# TigardBR.net
KiCad netlist of a schematic drawn in EAGLE
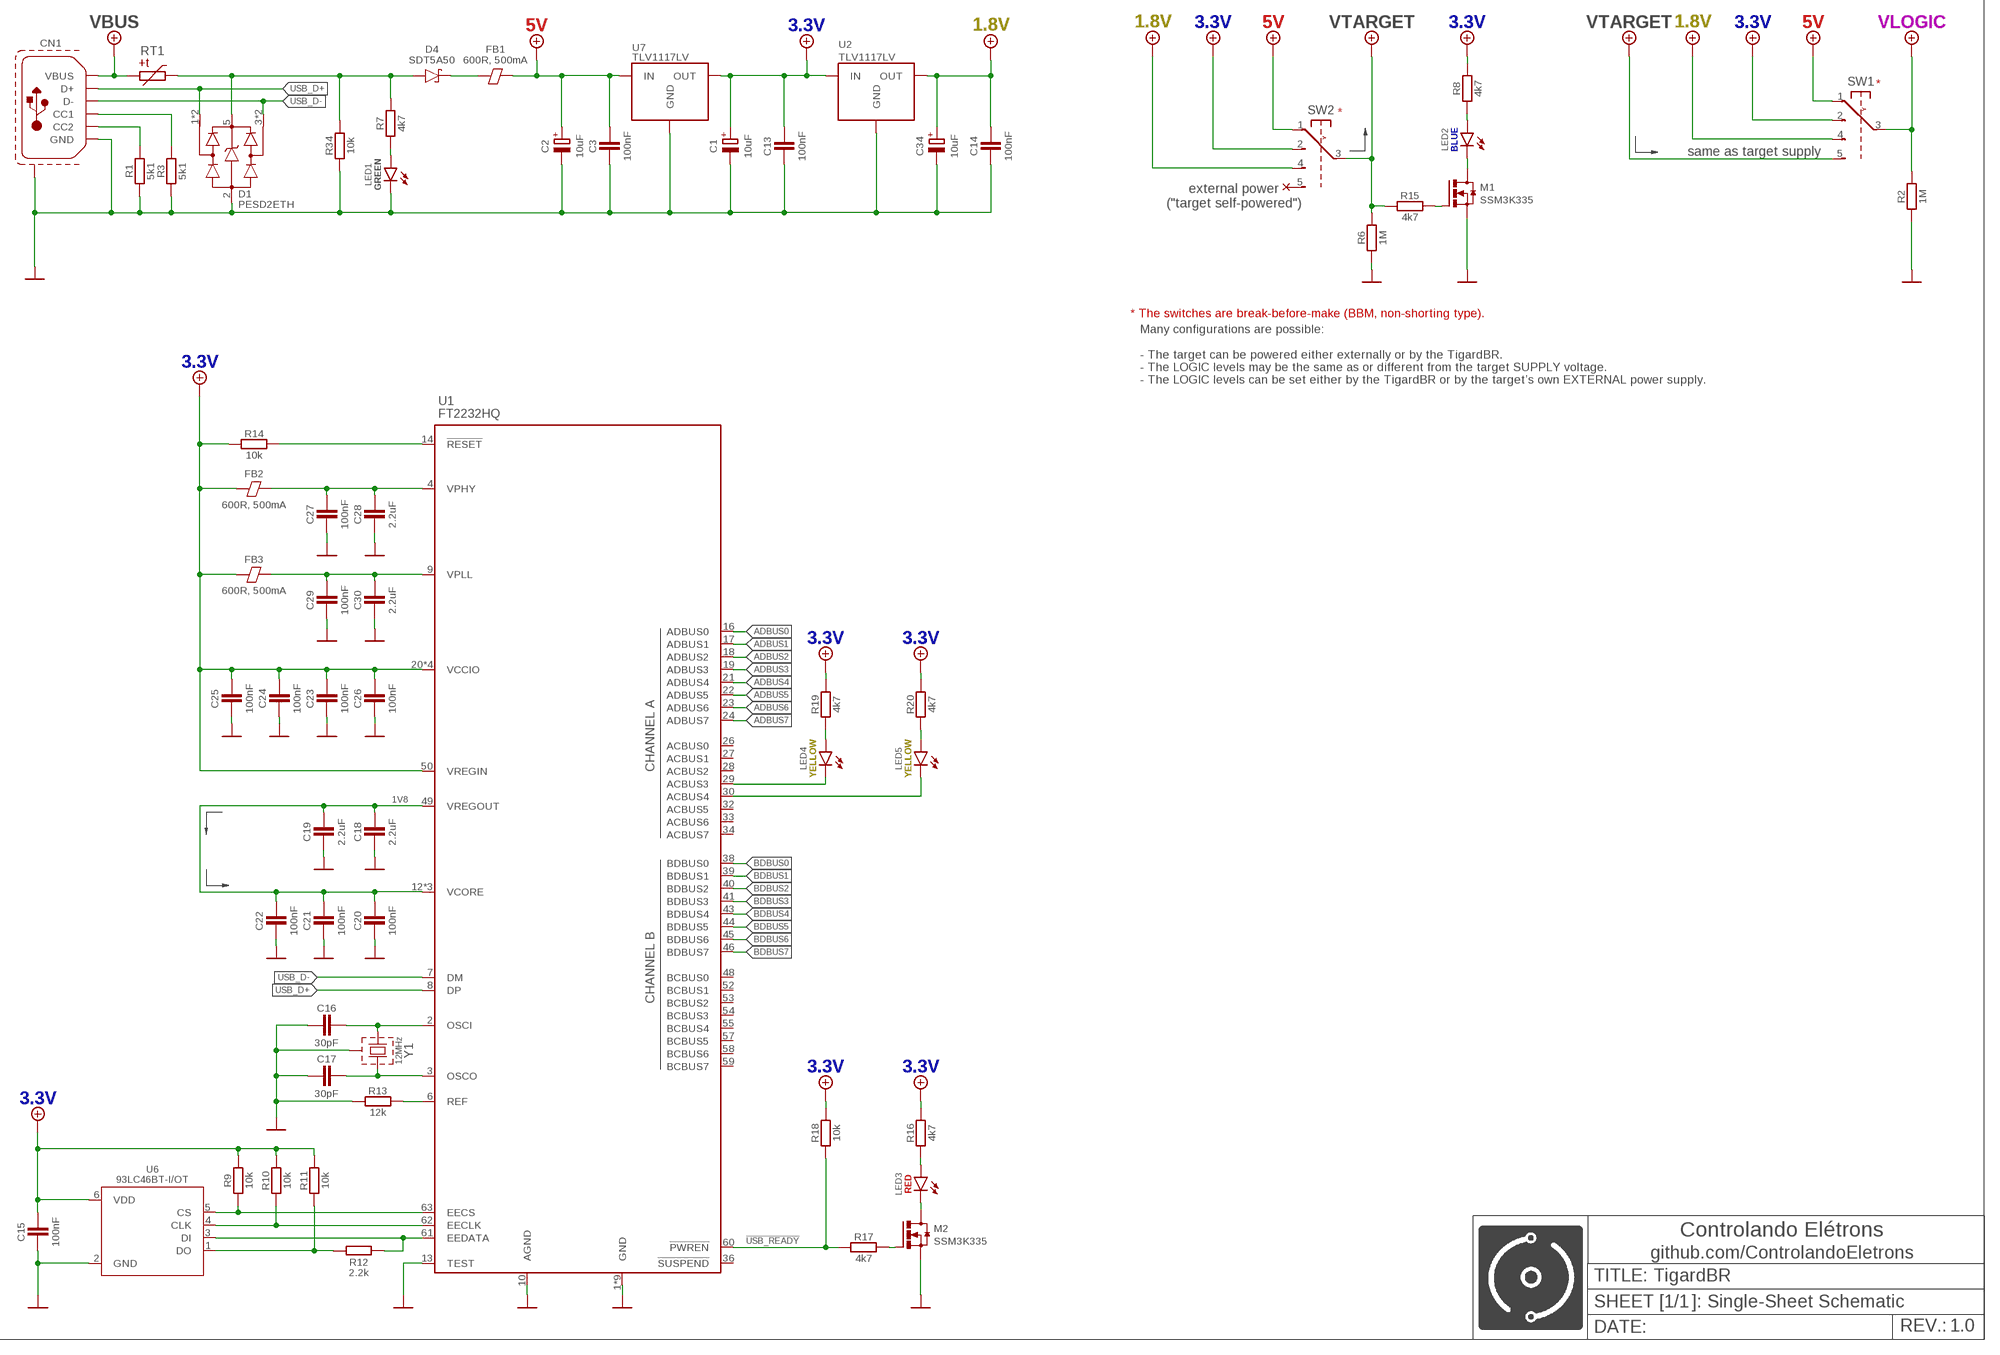
[diagram p0: schematic, sheet 1, part 1 of 3]
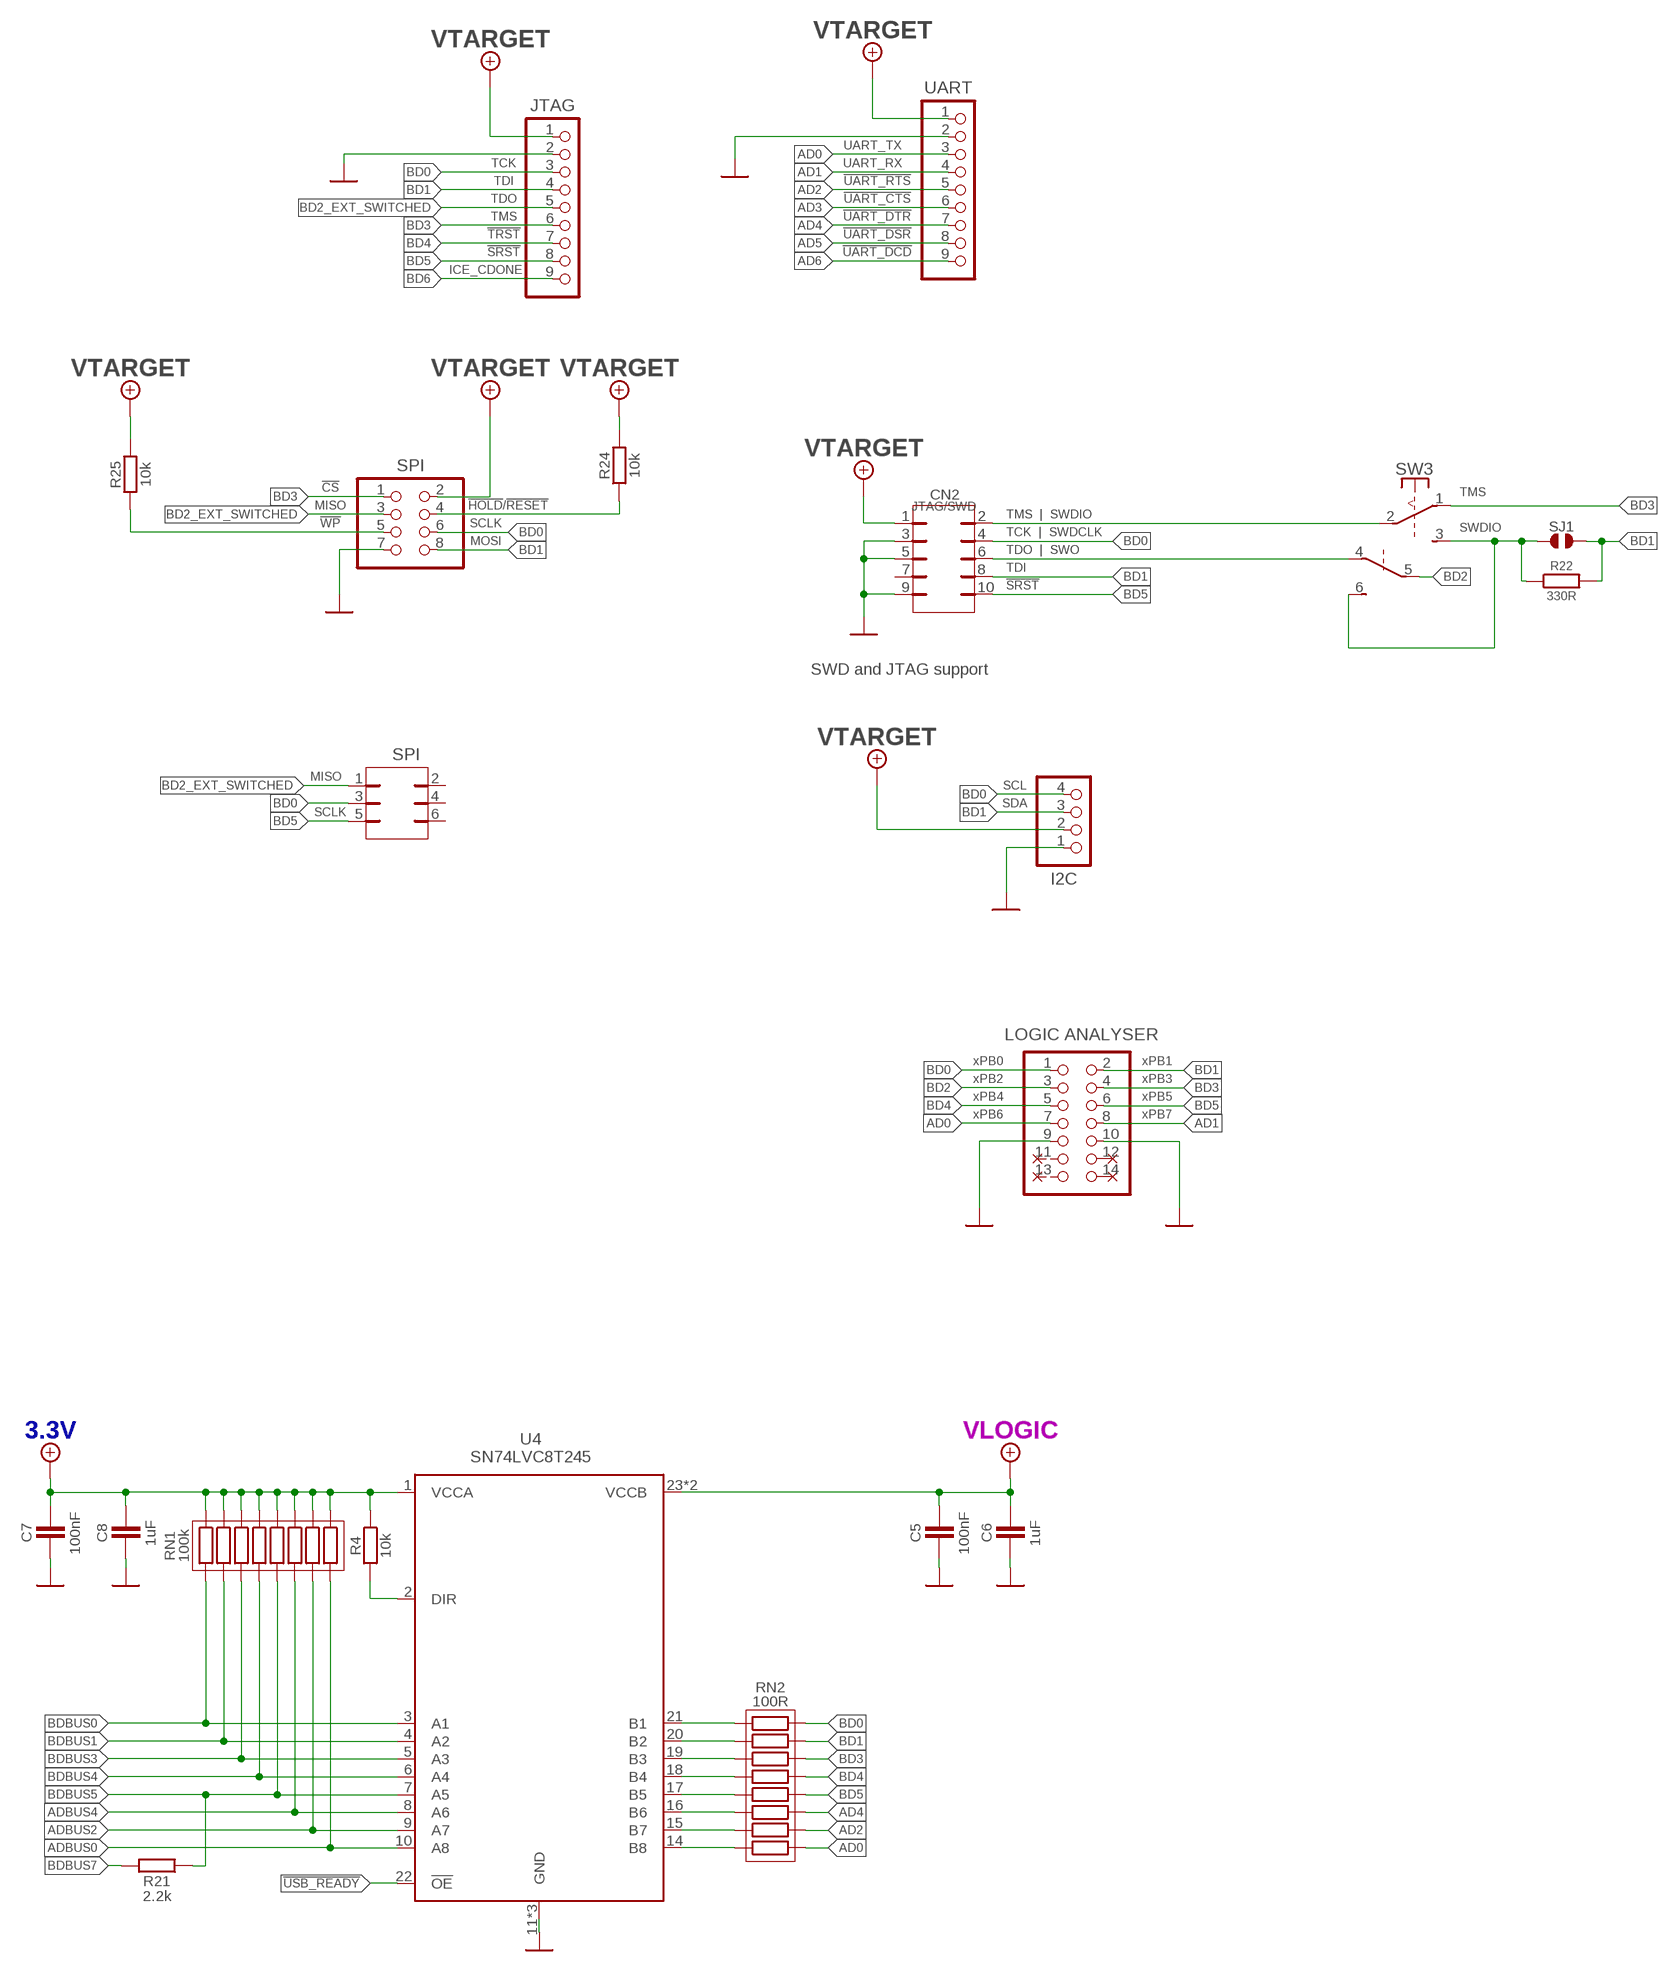
[diagram p1: schematic, sheet 1, part 2 of 3]
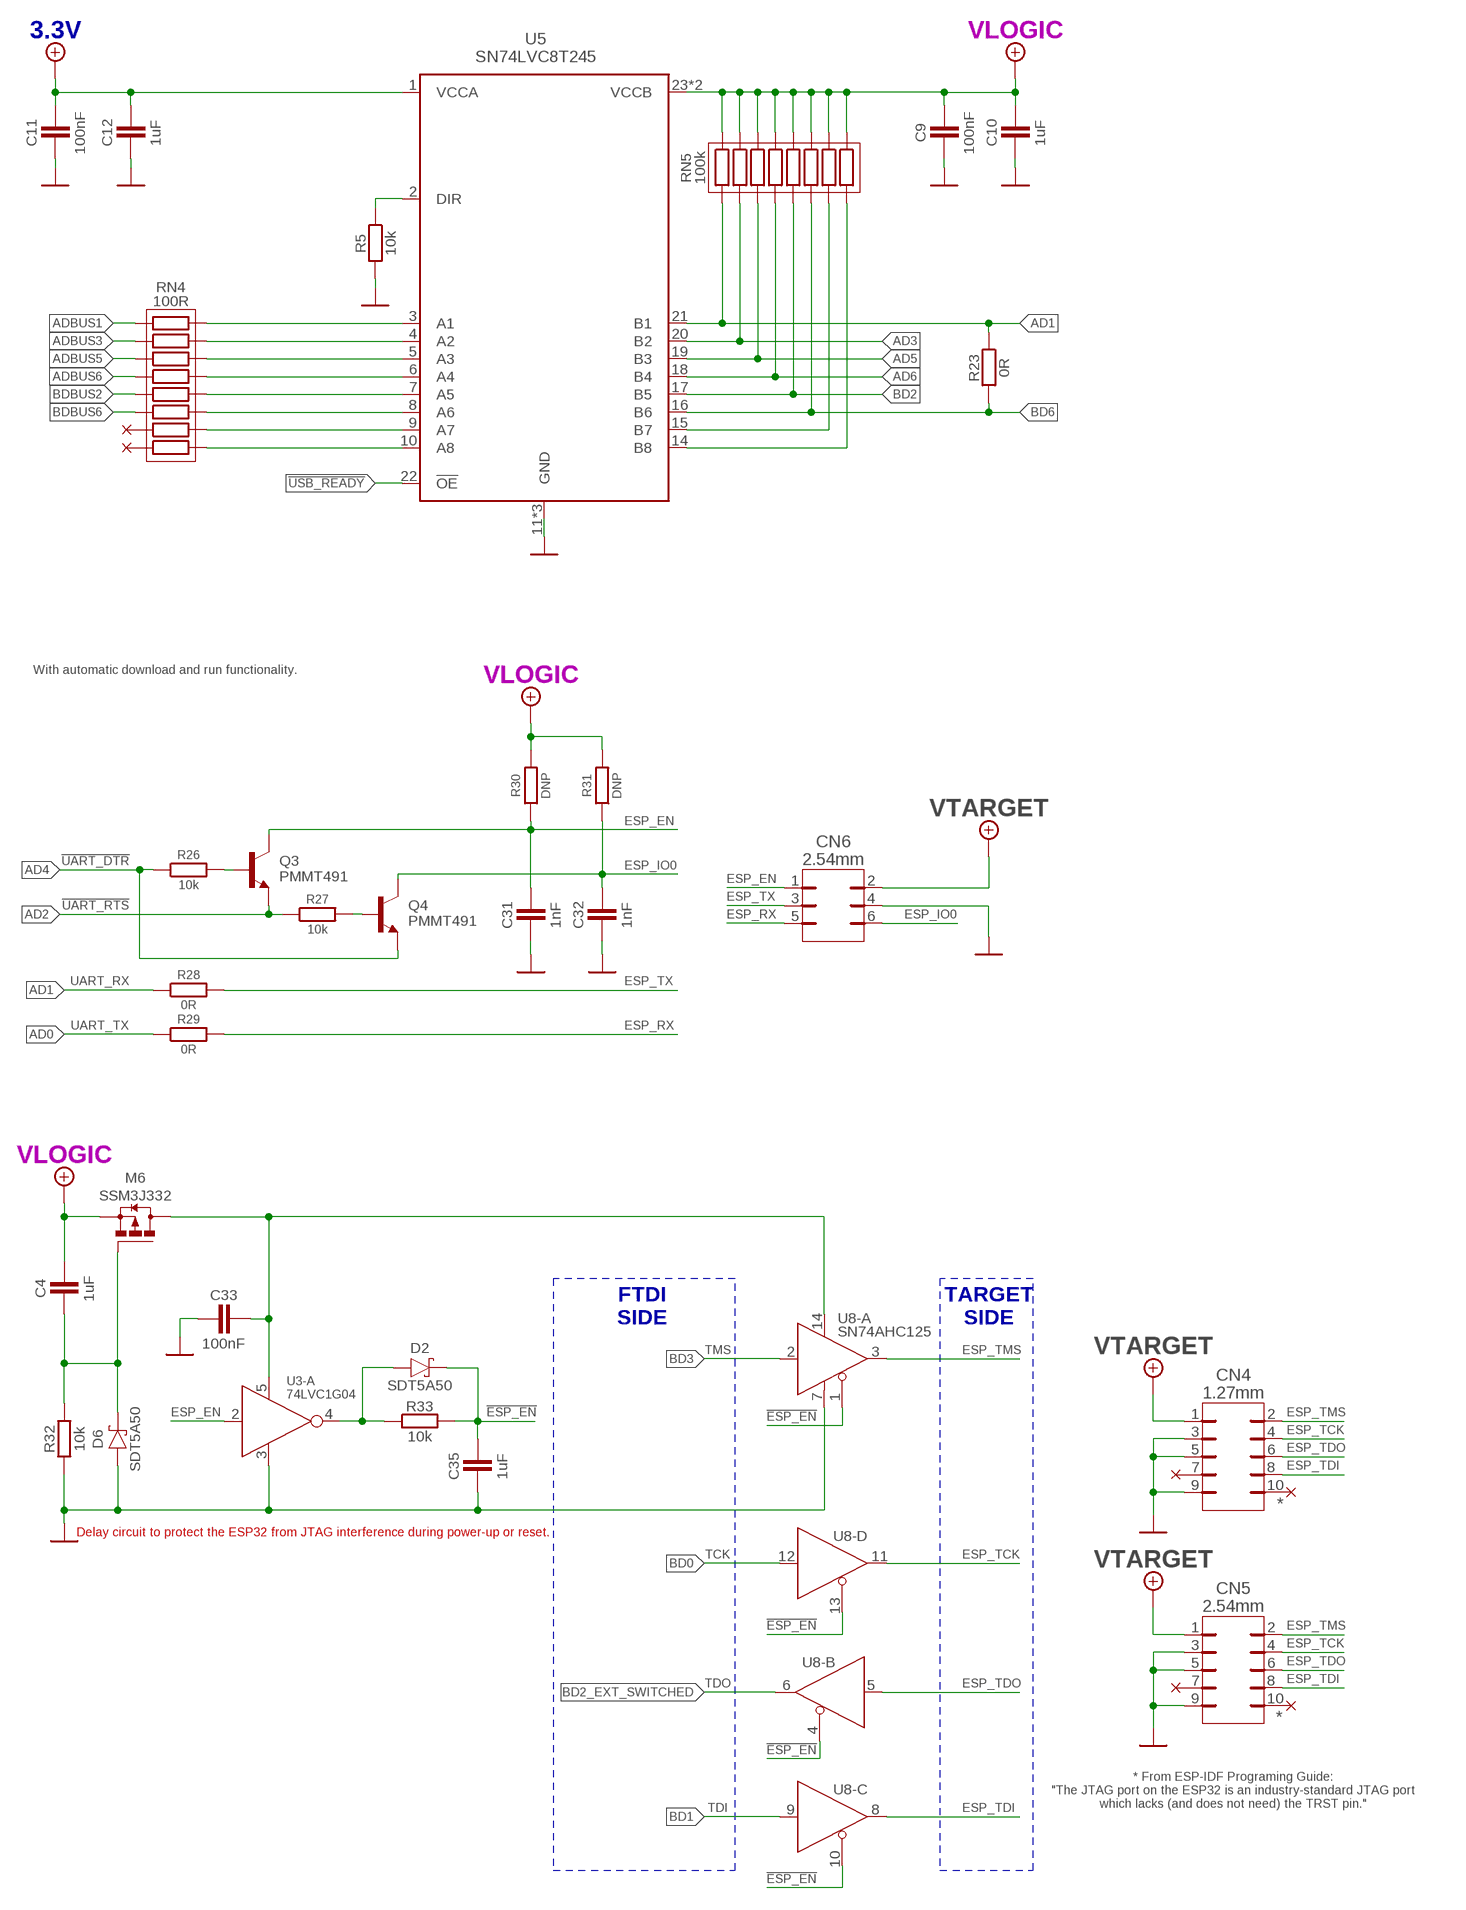
[diagram p2: schematic, sheet 1, part 3 of 3]

(export (version "E")
  (design (tool "Eeschema 10.0.6"))
  (components
    (comp (ref "C1")
      (value "10uF")
      (footprint "eagle-import:C1206_POL")
      (libsource (lib "eagle-import") (part "CP_1206_POL"))
    )
    (comp (ref "C2")
      (value "10uF")
      (footprint "eagle-import:C1206_POL")
      (libsource (lib "eagle-import") (part "CP_1206_POL"))
    )
    (comp (ref "C3")
      (value "100nF")
      (footprint "eagle-import:C0603")
      (libsource (lib "eagle-import") (part "C_0603"))
    )
    (comp (ref "C4")
      (value "1uF")
      (footprint "eagle-import:C0603")
      (libsource (lib "eagle-import") (part "C_0603"))
    )
    (comp (ref "C5")
      (value "100nF")
      (footprint "eagle-import:C0603")
      (libsource (lib "eagle-import") (part "C_0603"))
    )
    (comp (ref "C6")
      (value "1uF")
      (footprint "eagle-import:C0603")
      (libsource (lib "eagle-import") (part "C_0603"))
    )
    (comp (ref "C7")
      (value "100nF")
      (footprint "eagle-import:C0603")
      (libsource (lib "eagle-import") (part "C_0603"))
    )
    (comp (ref "C8")
      (value "1uF")
      (footprint "eagle-import:C0603")
      (libsource (lib "eagle-import") (part "C_0603"))
    )
    (comp (ref "C9")
      (value "100nF")
      (footprint "eagle-import:C0603")
      (libsource (lib "eagle-import") (part "C_0603"))
    )
    (comp (ref "C10")
      (value "1uF")
      (footprint "eagle-import:C0603")
      (libsource (lib "eagle-import") (part "C_0603"))
    )
    (comp (ref "C11")
      (value "100nF")
      (footprint "eagle-import:C0603")
      (libsource (lib "eagle-import") (part "C_0603"))
    )
    (comp (ref "C12")
      (value "1uF")
      (footprint "eagle-import:C0603")
      (libsource (lib "eagle-import") (part "C_0603"))
    )
    (comp (ref "C13")
      (value "100nF")
      (footprint "eagle-import:C0603")
      (libsource (lib "eagle-import") (part "C_0603"))
    )
    (comp (ref "C14")
      (value "100nF")
      (footprint "eagle-import:C0603")
      (libsource (lib "eagle-import") (part "C_0603"))
    )
    (comp (ref "C15")
      (value "100nF")
      (footprint "eagle-import:C0603")
      (libsource (lib "eagle-import") (part "C_0603"))
    )
    (comp (ref "C16")
      (value "30pF")
      (footprint "eagle-import:C0603")
      (libsource (lib "eagle-import") (part "C_0603"))
    )
    (comp (ref "C17")
      (value "30pF")
      (footprint "eagle-import:C0603")
      (libsource (lib "eagle-import") (part "C_0603"))
    )
    (comp (ref "C18")
      (value "2.2uF")
      (footprint "eagle-import:C0603")
      (libsource (lib "eagle-import") (part "C_0603"))
    )
    (comp (ref "C19")
      (value "2.2uF")
      (footprint "eagle-import:C0603")
      (libsource (lib "eagle-import") (part "C_0603"))
    )
    (comp (ref "C20")
      (value "100nF")
      (footprint "eagle-import:C0603")
      (libsource (lib "eagle-import") (part "C_0603"))
    )
    (comp (ref "C21")
      (value "100nF")
      (footprint "eagle-import:C0603")
      (libsource (lib "eagle-import") (part "C_0603"))
    )
    (comp (ref "C22")
      (value "100nF")
      (footprint "eagle-import:C0603")
      (libsource (lib "eagle-import") (part "C_0603"))
    )
    (comp (ref "C23")
      (value "100nF")
      (footprint "eagle-import:C0603")
      (libsource (lib "eagle-import") (part "C_0603"))
    )
    (comp (ref "C24")
      (value "100nF")
      (footprint "eagle-import:C0603")
      (libsource (lib "eagle-import") (part "C_0603"))
    )
    (comp (ref "C25")
      (value "100nF")
      (footprint "eagle-import:C0603")
      (libsource (lib "eagle-import") (part "C_0603"))
    )
    (comp (ref "C26")
      (value "100nF")
      (footprint "eagle-import:C0603")
      (libsource (lib "eagle-import") (part "C_0603"))
    )
    (comp (ref "C27")
      (value "100nF")
      (footprint "eagle-import:C0603")
      (libsource (lib "eagle-import") (part "C_0603"))
    )
    (comp (ref "C28")
      (value "2.2uF")
      (footprint "eagle-import:C0603")
      (libsource (lib "eagle-import") (part "C_0603"))
    )
    (comp (ref "C29")
      (value "100nF")
      (footprint "eagle-import:C0603")
      (libsource (lib "eagle-import") (part "C_0603"))
    )
    (comp (ref "C30")
      (value "2.2uF")
      (footprint "eagle-import:C0603")
      (libsource (lib "eagle-import") (part "C_0603"))
    )
    (comp (ref "C31")
      (value "1nF")
      (footprint "eagle-import:C0603")
      (libsource (lib "eagle-import") (part "C_0603"))
    )
    (comp (ref "C32")
      (value "1nF")
      (footprint "eagle-import:C0603")
      (libsource (lib "eagle-import") (part "C_0603"))
    )
    (comp (ref "C33")
      (value "100nF")
      (footprint "eagle-import:C0603")
      (libsource (lib "eagle-import") (part "C_0603"))
    )
    (comp (ref "C34")
      (value "10uF")
      (footprint "eagle-import:C1206_POL")
      (libsource (lib "eagle-import") (part "CP_1206_POL"))
    )
    (comp (ref "C35")
      (value "1uF")
      (footprint "eagle-import:C0603")
      (libsource (lib "eagle-import") (part "C_0603"))
    )
    (comp (ref "CN1")
      (value "USB-C-16P")
      (footprint "eagle-import:USB-C-16P")
      (libsource (lib "eagle-import") (part "USB-C-16P"))
    )
    (comp (ref "CN2")
      (value "JTAG/SWD")
      (footprint "eagle-import:JTAG-ARM-10P")
      (fields (field (name "PN") "20021121-00010C4LF"))
      (libsource (lib "eagle-import") (part "JTAG"))
    )
    (comp (ref "CN3")
      (value "I2C")
      (footprint "eagle-import:1X04")
      (libsource (lib "eagle-import") (part "PINHD-1X04_2.54"))
    )
    (comp (ref "CN4")
      (value "1.27mm")
      (footprint "eagle-import:JTAG-ARM-10P")
      (fields (field (name "PN") "20021121-00010C4LF"))
      (libsource (lib "eagle-import") (part "JTAG"))
    )
    (comp (ref "CN5")
      (value "2.54mm")
      (footprint "eagle-import:2X05")
      (libsource (lib "eagle-import") (part "PINHD-2X05_2.54"))
    )
    (comp (ref "CN6")
      (value "2.54mm")
      (footprint "eagle-import:2X03")
      (libsource (lib "eagle-import") (part "PINHD-2X03_2.54"))
    )
    (comp (ref "D1")
      (value "TVS-ARRAY-2")
      (footprint "eagle-import:TSOP-6")
      (fields (field (name "FAMILY") "PESD2ETH"))
      (libsource (lib "eagle-import") (part "TVS-ARRAY-2"))
    )
    (comp (ref "D2")
      (value "SDT5A50")
      (footprint "eagle-import:DO-214AC")
      (libsource (lib "eagle-import") (part "SCHOTTKY-SDT5A50SA"))
    )
    (comp (ref "D4")
      (value "SDT5A50")
      (footprint "eagle-import:DO-214AC")
      (libsource (lib "eagle-import") (part "SCHOTTKY-SDT5A50SA"))
    )
    (comp (ref "D6")
      (value "SDT5A50")
      (footprint "eagle-import:DO-214AC")
      (libsource (lib "eagle-import") (part "SCHOTTKY-SDT5A50SA"))
    )
    (comp (ref "FB1")
      (value "600R, 500mA")
      (footprint "eagle-import:L0603")
      (libsource (lib "eagle-import") (part "FB_0603"))
    )
    (comp (ref "FB2")
      (value "600R, 500mA")
      (footprint "eagle-import:L0603")
      (libsource (lib "eagle-import") (part "FB_0603"))
    )
    (comp (ref "FB3")
      (value "600R, 500mA")
      (footprint "eagle-import:L0603")
      (libsource (lib "eagle-import") (part "FB_0603"))
    )
    (comp (ref "JP1")
      (value "JTAG")
      (footprint "eagle-import:1X09")
      (libsource (lib "eagle-import") (part "PINHD-1X09_2.54"))
    )
    (comp (ref "JP2")
      (value "SPI")
      (footprint "eagle-import:2X04")
      (libsource (lib "eagle-import") (part "PINHD-2X04_2.54"))
    )
    (comp (ref "JP3")
      (value "UART")
      (footprint "eagle-import:1X09")
      (libsource (lib "eagle-import") (part "PINHD-1X09_2.54"))
    )
    (comp (ref "JP4")
      (value "LOGIC ANALYSER")
      (footprint "eagle-import:2X07")
      (libsource (lib "eagle-import") (part "PINHD-2X07_2.54"))
    )
    (comp (ref "JP5")
      (value "SPI")
      (footprint "eagle-import:2X03")
      (libsource (lib "eagle-import") (part "PINHD-2X03_2.54"))
    )
    (comp (ref "LED1")
      (value "GREEN")
      (footprint "eagle-import:L0603G")
      (libsource (lib "eagle-import") (part "LED-0603-G"))
    )
    (comp (ref "LED2")
      (value "BLUE")
      (footprint "eagle-import:L0603B")
      (libsource (lib "eagle-import") (part "LED-0603-B"))
    )
    (comp (ref "LED3")
      (value "RED")
      (footprint "eagle-import:L0603R")
      (libsource (lib "eagle-import") (part "LED-0603-R"))
    )
    (comp (ref "LED4")
      (value "YELLOW")
      (footprint "eagle-import:L0603Y")
      (libsource (lib "eagle-import") (part "LED-0603-Y"))
    )
    (comp (ref "LED5")
      (value "YELLOW")
      (footprint "eagle-import:L0603Y")
      (libsource (lib "eagle-import") (part "LED-0603-Y"))
    )
    (comp (ref "M1")
      (value "SSM3K335")
      (footprint "eagle-import:SOT23-3")
      (libsource (lib "eagle-import") (part "MOSFET-N-SSM3K335R"))
    )
    (comp (ref "M2")
      (value "SSM3K335")
      (footprint "eagle-import:SOT23-3")
      (libsource (lib "eagle-import") (part "MOSFET-N-SSM3K335R"))
    )
    (comp (ref "M6")
      (value "SSM3J332")
      (footprint "eagle-import:SOT23-3")
      (libsource (lib "eagle-import") (part "MOSFET-P-SSM3J332R"))
    )
    (comp (ref "Q3")
      (value "PMMT491")
      (footprint "eagle-import:SOT23-3")
      (libsource (lib "eagle-import") (part "BJT-N-PMMT491"))
    )
    (comp (ref "Q4")
      (value "PMMT491")
      (footprint "eagle-import:SOT23-3")
      (libsource (lib "eagle-import") (part "BJT-N-PMMT491"))
    )
    (comp (ref "R1")
      (value "5k1")
      (footprint "eagle-import:R0603")
      (libsource (lib "eagle-import") (part "R_0603"))
    )
    (comp (ref "R2")
      (value "1M")
      (footprint "eagle-import:R0603")
      (libsource (lib "eagle-import") (part "R_0603"))
    )
    (comp (ref "R3")
      (value "5k1")
      (footprint "eagle-import:R0603")
      (libsource (lib "eagle-import") (part "R_0603"))
    )
    (comp (ref "R4")
      (value "10k")
      (footprint "eagle-import:R0603")
      (libsource (lib "eagle-import") (part "R_0603"))
    )
    (comp (ref "R5")
      (value "10k")
      (footprint "eagle-import:R0603")
      (libsource (lib "eagle-import") (part "R_0603"))
    )
    (comp (ref "R6")
      (value "1M")
      (footprint "eagle-import:R0603")
      (libsource (lib "eagle-import") (part "R_0603"))
    )
    (comp (ref "R7")
      (value "4k7")
      (footprint "eagle-import:R0603")
      (libsource (lib "eagle-import") (part "R_0603"))
    )
    (comp (ref "R8")
      (value "4k7")
      (footprint "eagle-import:R0603")
      (libsource (lib "eagle-import") (part "R_0603"))
    )
    (comp (ref "R9")
      (value "10k")
      (footprint "eagle-import:R0603")
      (libsource (lib "eagle-import") (part "R_0603"))
    )
    (comp (ref "R10")
      (value "10k")
      (footprint "eagle-import:R0603")
      (libsource (lib "eagle-import") (part "R_0603"))
    )
    (comp (ref "R11")
      (value "10k")
      (footprint "eagle-import:R0603")
      (libsource (lib "eagle-import") (part "R_0603"))
    )
    (comp (ref "R12")
      (value "2.2k")
      (footprint "eagle-import:R0603")
      (libsource (lib "eagle-import") (part "R_0603"))
    )
    (comp (ref "R13")
      (value "12k")
      (footprint "eagle-import:R0603")
      (libsource (lib "eagle-import") (part "R_0603"))
    )
    (comp (ref "R14")
      (value "10k")
      (footprint "eagle-import:R0603")
      (libsource (lib "eagle-import") (part "R_0603"))
    )
    (comp (ref "R15")
      (value "4k7")
      (footprint "eagle-import:R0603")
      (libsource (lib "eagle-import") (part "R_0603"))
    )
    (comp (ref "R16")
      (value "4k7")
      (footprint "eagle-import:R0603")
      (libsource (lib "eagle-import") (part "R_0603"))
    )
    (comp (ref "R17")
      (value "4k7")
      (footprint "eagle-import:R0603")
      (libsource (lib "eagle-import") (part "R_0603"))
    )
    (comp (ref "R18")
      (value "10k")
      (footprint "eagle-import:R0603")
      (libsource (lib "eagle-import") (part "R_0603"))
    )
    (comp (ref "R19")
      (value "4k7")
      (footprint "eagle-import:R0603")
      (libsource (lib "eagle-import") (part "R_0603"))
    )
    (comp (ref "R20")
      (value "4k7")
      (footprint "eagle-import:R0603")
      (libsource (lib "eagle-import") (part "R_0603"))
    )
    (comp (ref "R21")
      (value "2.2k")
      (footprint "eagle-import:R0603")
      (libsource (lib "eagle-import") (part "R_0603"))
    )
    (comp (ref "R22")
      (value "330R")
      (footprint "eagle-import:R0603")
      (libsource (lib "eagle-import") (part "R_0603"))
    )
    (comp (ref "R23")
      (value "0R")
      (footprint "eagle-import:R0603")
      (libsource (lib "eagle-import") (part "R_0603"))
    )
    (comp (ref "R24")
      (value "10k")
      (footprint "eagle-import:R0603")
      (libsource (lib "eagle-import") (part "R_0603"))
    )
    (comp (ref "R25")
      (value "10k")
      (footprint "eagle-import:R0603")
      (libsource (lib "eagle-import") (part "R_0603"))
    )
    (comp (ref "R26")
      (value "10k")
      (footprint "eagle-import:R0603")
      (libsource (lib "eagle-import") (part "R_0603"))
    )
    (comp (ref "R27")
      (value "10k")
      (footprint "eagle-import:R0603")
      (libsource (lib "eagle-import") (part "R_0603"))
    )
    (comp (ref "R28")
      (value "0R")
      (footprint "eagle-import:R0603")
      (libsource (lib "eagle-import") (part "R_0603"))
    )
    (comp (ref "R29")
      (value "0R")
      (footprint "eagle-import:R0603")
      (libsource (lib "eagle-import") (part "R_0603"))
    )
    (comp (ref "R30")
      (value "DNP")
      (footprint "eagle-import:R0603")
      (libsource (lib "eagle-import") (part "R_0603"))
    )
    (comp (ref "R31")
      (value "DNP")
      (footprint "eagle-import:R0603")
      (libsource (lib "eagle-import") (part "R_0603"))
    )
    (comp (ref "R32")
      (value "10k")
      (footprint "eagle-import:R0603")
      (libsource (lib "eagle-import") (part "R_0603"))
    )
    (comp (ref "R33")
      (value "10k")
      (footprint "eagle-import:R0603")
      (libsource (lib "eagle-import") (part "R_0603"))
    )
    (comp (ref "R34")
      (value "10k")
      (footprint "eagle-import:R0603")
      (libsource (lib "eagle-import") (part "R_0603"))
    )
    (comp (ref "RN1")
      (value "100k")
      (footprint "eagle-import:RN0602")
      (libsource (lib "eagle-import") (part "RN_"))
    )
    (comp (ref "RN2")
      (value "100R")
      (footprint "eagle-import:RN0602")
      (libsource (lib "eagle-import") (part "RN_"))
    )
    (comp (ref "RN4")
      (value "100R")
      (footprint "eagle-import:RN0602")
      (libsource (lib "eagle-import") (part "RN_"))
    )
    (comp (ref "RN5")
      (value "100k")
      (footprint "eagle-import:RN0602")
      (libsource (lib "eagle-import") (part "RN_"))
    )
    (comp (ref "RT1")
      (value "PTC-")
      (footprint "eagle-import:F1812")
      (fields (field (name "TYPE") "+t"))
      (libsource (lib "eagle-import") (part "PTC-"))
    )
    (comp (ref "SJ1")
      (value "2P-NO")
      (footprint "eagle-import:2P-NO-0603")
      (libsource (lib "eagle-import") (part "2P-NO"))
    )
    (comp (ref "SW1")
      (value "DP4T-")
      (footprint "eagle-import:SSSS224100")
      (libsource (lib "eagle-import") (part "DP4T-"))
    )
    (comp (ref "SW2")
      (value "DP4T-")
      (footprint "eagle-import:SSSS224100")
      (libsource (lib "eagle-import") (part "DP4T-"))
    )
    (comp (ref "SW3")
      (value "DP2T-STRAIGHT-SMD")
      (footprint "eagle-import:JS202011SCQN")
      (libsource (lib "eagle-import") (part "DP2T-STRAIGHT-SMD"))
    )
    (comp (ref "U1")
      (value "FT2232HQ")
      (footprint "eagle-import:QFN-64")
      (libsource (lib "eagle-import") (part "FT2232HQ"))
    )
    (comp (ref "U2")
      (value "TLV1117LV")
      (footprint "eagle-import:SOT-223-3")
      (fields (field (name "PN") "TLV1117LV18DCYR"))
      (libsource (lib "eagle-import") (part "1117-3.3V"))
    )
    (comp (ref "U3")
      (value "74LVC1G04")
      (footprint "eagle-import:SOT753-5_(SC-74A)")
      (libsource (lib "eagle-import") (part "SINGLE-INVERTER-74LVC1G04GV"))
    )
    (comp (ref "U4")
      (value "SN74LVC8T245")
      (footprint "eagle-import:TSSOP-24")
      (libsource (lib "eagle-import") (part "SN74LVC8T245"))
    )
    (comp (ref "U5")
      (value "SN74LVC8T245")
      (footprint "eagle-import:TSSOP-24")
      (libsource (lib "eagle-import") (part "SN74LVC8T245"))
    )
    (comp (ref "U6")
      (value "93LC46BT-I/OT")
      (footprint "eagle-import:SOT23-6")
      (libsource (lib "eagle-import") (part "93LC46BT-I/OT"))
    )
    (comp (ref "U7")
      (value "TLV1117LV")
      (footprint "eagle-import:SOT-223-3")
      (libsource (lib "eagle-import") (part "1117-3.3V"))
    )
    (comp (ref "U8")
      (value "SN74AHC125")
      (footprint "eagle-import:SOIC-14")
      (libsource (lib "eagle-import") (part "QUAD-BUFFER-"))
    )
    (comp (ref "Y1")
      (value "12MHz")
      (footprint "eagle-import:3.2MM_2.5MM")
      (libsource (lib "eagle-import") (part "OSC-CHASSI-"))
    )
  )
  (nets
    (net (code "1") (name "/1V8") (class "Default")
      (node (ref "C18") (pin "1") (pinfunction "1_1") (pintype "passive"))
      (node (ref "C19") (pin "1") (pinfunction "1_1") (pintype "passive"))
      (node (ref "C20") (pin "1") (pinfunction "1_1") (pintype "passive"))
      (node (ref "C21") (pin "1") (pinfunction "1_1") (pintype "passive"))
      (node (ref "C22") (pin "1") (pinfunction "1_1") (pintype "passive"))
      (node (ref "U1") (pin "12") (pinfunction "VCORE_12") (pintype "bidirectional"))
      (node (ref "U1") (pin "37") (pinfunction "VCORE_37") (pintype "bidirectional"))
      (node (ref "U1") (pin "49") (pinfunction "VREGOUT_49") (pintype "bidirectional"))
      (node (ref "U1") (pin "64") (pinfunction "VCORE_64") (pintype "bidirectional"))
    )
    (net (code "2") (name "/ESP_EN") (class "Default")
      (node (ref "C31") (pin "1") (pinfunction "1_1") (pintype "passive"))
      (node (ref "CN6") (pin "1") (pinfunction "1_1") (pintype "passive"))
      (node (ref "Q3") (pin "3") (pinfunction "C_3") (pintype "passive"))
      (node (ref "R30") (pin "1") (pinfunction "1_1") (pintype "passive"))
      (node (ref "U3") (pin "2") (pinfunction "A_2") (pintype "bidirectional"))
    )
    (net (code "3") (name "/ESP_IO0") (class "Default")
      (node (ref "C32") (pin "1") (pinfunction "1_1") (pintype "passive"))
      (node (ref "CN6") (pin "6") (pinfunction "6_6") (pintype "passive"))
      (node (ref "Q4") (pin "3") (pinfunction "C_3") (pintype "passive"))
      (node (ref "R31") (pin "1") (pinfunction "1_1") (pintype "passive"))
    )
    (net (code "4") (name "/ESP_RX") (class "Default")
      (node (ref "CN6") (pin "5") (pinfunction "5_5") (pintype "passive"))
      (node (ref "R29") (pin "2") (pinfunction "2_2") (pintype "passive"))
    )
    (net (code "5") (name "/ESP_TCK") (class "Default")
      (node (ref "CN4") (pin "4") (pinfunction "TCK_4") (pintype "bidirectional"))
      (node (ref "CN5") (pin "4") (pinfunction "4_4") (pintype "passive"))
      (node (ref "U8") (pin "11") (pinfunction "Y_11") (pintype "bidirectional"))
    )
    (net (code "6") (name "/ESP_TDI") (class "Default")
      (node (ref "CN4") (pin "8") (pinfunction "TDI_8") (pintype "bidirectional"))
      (node (ref "CN5") (pin "8") (pinfunction "8_8") (pintype "passive"))
      (node (ref "U8") (pin "8") (pinfunction "Y_8") (pintype "bidirectional"))
    )
    (net (code "7") (name "/ESP_TDO") (class "Default")
      (node (ref "CN4") (pin "6") (pinfunction "TDO_6") (pintype "bidirectional"))
      (node (ref "CN5") (pin "6") (pinfunction "6_6") (pintype "passive"))
      (node (ref "U8") (pin "5") (pinfunction "A_5") (pintype "bidirectional"))
    )
    (net (code "8") (name "/ESP_TMS") (class "Default")
      (node (ref "CN4") (pin "2") (pinfunction "TMS_2") (pintype "bidirectional"))
      (node (ref "CN5") (pin "2") (pinfunction "2_2") (pintype "passive"))
      (node (ref "U8") (pin "3") (pinfunction "Y_3") (pintype "bidirectional"))
    )
    (net (code "9") (name "/ESP_TX") (class "Default")
      (node (ref "CN6") (pin "3") (pinfunction "3_3") (pintype "passive"))
      (node (ref "R28") (pin "2") (pinfunction "2_2") (pintype "passive"))
    )
    (net (code "10") (name "/~{ESP_EN}") (class "Default")
      (node (ref "C35") (pin "1") (pinfunction "1_1") (pintype "passive"))
      (node (ref "D2") (pin "1") (pinfunction "K_1") (pintype "passive"))
      (node (ref "R33") (pin "2") (pinfunction "2_2") (pintype "passive"))
      (node (ref "U8") (pin "1") (pinfunction "~{OE}_1") (pintype "bidirectional"))
      (node (ref "U8") (pin "10") (pinfunction "~{OE}_10") (pintype "bidirectional"))
      (node (ref "U8") (pin "13") (pinfunction "~{OE}_13") (pintype "bidirectional"))
      (node (ref "U8") (pin "4") (pinfunction "~{OE}_4") (pintype "bidirectional"))
    )
    (net (code "11") (name "/~{USB_READY}") (class "Default")
      (node (ref "R17") (pin "1") (pinfunction "1_1") (pintype "passive"))
      (node (ref "R18") (pin "2") (pinfunction "2_2") (pintype "passive"))
      (node (ref "U1") (pin "60") (pinfunction "~{PWREN}_60") (pintype "bidirectional"))
      (node (ref "U4") (pin "22") (pinfunction "~{OE}_22") (pintype "bidirectional"))
      (node (ref "U5") (pin "22") (pinfunction "~{OE}_22") (pintype "bidirectional"))
    )
    (net (code "12") (name "0V") (class "Default")
      (node (ref "C1") (pin "2") (pinfunction "-_2") (pintype "passive"))
      (node (ref "C10") (pin "2") (pinfunction "2_2") (pintype "passive"))
      (node (ref "C11") (pin "2") (pinfunction "2_2") (pintype "passive"))
      (node (ref "C12") (pin "2") (pinfunction "2_2") (pintype "passive"))
      (node (ref "C13") (pin "2") (pinfunction "2_2") (pintype "passive"))
      (node (ref "C14") (pin "2") (pinfunction "2_2") (pintype "passive"))
      (node (ref "C15") (pin "2") (pinfunction "2_2") (pintype "passive"))
      (node (ref "C16") (pin "2") (pinfunction "2_2") (pintype "passive"))
      (node (ref "C17") (pin "2") (pinfunction "2_2") (pintype "passive"))
      (node (ref "C18") (pin "2") (pinfunction "2_2") (pintype "passive"))
      (node (ref "C19") (pin "2") (pinfunction "2_2") (pintype "passive"))
      (node (ref "C2") (pin "2") (pinfunction "-_2") (pintype "passive"))
      (node (ref "C20") (pin "2") (pinfunction "2_2") (pintype "passive"))
      (node (ref "C21") (pin "2") (pinfunction "2_2") (pintype "passive"))
      (node (ref "C22") (pin "2") (pinfunction "2_2") (pintype "passive"))
      (node (ref "C23") (pin "2") (pinfunction "2_2") (pintype "passive"))
      (node (ref "C24") (pin "2") (pinfunction "2_2") (pintype "passive"))
      (node (ref "C25") (pin "2") (pinfunction "2_2") (pintype "passive"))
      (node (ref "C26") (pin "2") (pinfunction "2_2") (pintype "passive"))
      (node (ref "C27") (pin "2") (pinfunction "2_2") (pintype "passive"))
      (node (ref "C28") (pin "2") (pinfunction "2_2") (pintype "passive"))
      (node (ref "C29") (pin "2") (pinfunction "2_2") (pintype "passive"))
      (node (ref "C3") (pin "2") (pinfunction "2_2") (pintype "passive"))
      (node (ref "C30") (pin "2") (pinfunction "2_2") (pintype "passive"))
      (node (ref "C31") (pin "2") (pinfunction "2_2") (pintype "passive"))
      (node (ref "C32") (pin "2") (pinfunction "2_2") (pintype "passive"))
      (node (ref "C33") (pin "2") (pinfunction "2_2") (pintype "passive"))
      (node (ref "C34") (pin "2") (pinfunction "-_2") (pintype "passive"))
      (node (ref "C35") (pin "2") (pinfunction "2_2") (pintype "passive"))
      (node (ref "C5") (pin "2") (pinfunction "2_2") (pintype "passive"))
      (node (ref "C6") (pin "2") (pinfunction "2_2") (pintype "passive"))
      (node (ref "C7") (pin "2") (pinfunction "2_2") (pintype "passive"))
      (node (ref "C8") (pin "2") (pinfunction "2_2") (pintype "passive"))
      (node (ref "C9") (pin "2") (pinfunction "2_2") (pintype "passive"))
      (node (ref "CN1") (pin "A1_B12") (pinfunction "GND_A1_B12") (pintype "bidirectional"))
      (node (ref "CN1") (pin "B1_A12") (pinfunction "GND_B1_A12") (pintype "bidirectional"))
      (node (ref "CN1") (pin "S1") (pinfunction "CHASSI_S1") (pintype "passive"))
      (node (ref "CN1") (pin "S2") (pinfunction "CHASSI_S2") (pintype "passive"))
      (node (ref "CN1") (pin "S3") (pinfunction "CHASSI_S3") (pintype "passive"))
      (node (ref "CN1") (pin "S4") (pinfunction "CHASSI_S4") (pintype "passive"))
      (node (ref "CN2") (pin "3") (pinfunction "GND_3") (pintype "bidirectional"))
      (node (ref "CN2") (pin "5") (pinfunction "GND2_5") (pintype "bidirectional"))
      (node (ref "CN2") (pin "9") (pinfunction "GND3_9") (pintype "bidirectional"))
      (node (ref "CN3") (pin "1") (pinfunction "1_1") (pintype "passive"))
      (node (ref "CN4") (pin "3") (pinfunction "GND_3") (pintype "bidirectional"))
      (node (ref "CN4") (pin "5") (pinfunction "GND2_5") (pintype "bidirectional"))
      (node (ref "CN4") (pin "9") (pinfunction "GND3_9") (pintype "bidirectional"))
      (node (ref "CN5") (pin "3") (pinfunction "3_3") (pintype "passive"))
      (node (ref "CN5") (pin "5") (pinfunction "5_5") (pintype "passive"))
      (node (ref "CN5") (pin "9") (pinfunction "9_9") (pintype "passive"))
      (node (ref "CN6") (pin "4") (pinfunction "4_4") (pintype "passive"))
      (node (ref "D1") (pin "2") (pinfunction "GND_2") (pintype "power_in"))
      (node (ref "D6") (pin "2") (pinfunction "A_2") (pintype "passive"))
      (node (ref "JP1") (pin "2") (pinfunction "2_2") (pintype "passive"))
      (node (ref "JP2") (pin "7") (pinfunction "7_7") (pintype "passive"))
      (node (ref "JP3") (pin "2") (pinfunction "2_2") (pintype "passive"))
      (node (ref "JP4") (pin "10") (pinfunction "10_10") (pintype "passive"))
      (node (ref "JP4") (pin "9") (pinfunction "9_9") (pintype "passive"))
      (node (ref "LED1") (pin "K") (pinfunction "K_K") (pintype "passive"))
      (node (ref "M1") (pin "2") (pinfunction "S_2") (pintype "passive"))
      (node (ref "M2") (pin "2") (pinfunction "S_2") (pintype "passive"))
      (node (ref "R1") (pin "1") (pinfunction "1_1") (pintype "passive"))
      (node (ref "R13") (pin "2") (pinfunction "2_2") (pintype "passive"))
      (node (ref "R2") (pin "1") (pinfunction "1_1") (pintype "passive"))
      (node (ref "R3") (pin "1") (pinfunction "1_1") (pintype "passive"))
      (node (ref "R32") (pin "1") (pinfunction "1_1") (pintype "passive"))
      (node (ref "R34") (pin "1") (pinfunction "1_1") (pintype "passive"))
      (node (ref "R5") (pin "2") (pinfunction "2_2") (pintype "passive"))
      (node (ref "R6") (pin "1") (pinfunction "1_1") (pintype "passive"))
      (node (ref "U1") (pin "1") (pinfunction "GND_1") (pintype "bidirectional"))
      (node (ref "U1") (pin "10") (pinfunction "AGND_10") (pintype "bidirectional"))
      (node (ref "U1") (pin "11") (pinfunction "GND_11") (pintype "bidirectional"))
      (node (ref "U1") (pin "13") (pinfunction "TEST_13") (pintype "bidirectional"))
      (node (ref "U1") (pin "15") (pinfunction "GND_15") (pintype "bidirectional"))
      (node (ref "U1") (pin "25") (pinfunction "GND_25") (pintype "bidirectional"))
      (node (ref "U1") (pin "35") (pinfunction "GND_35") (pintype "bidirectional"))
      (node (ref "U1") (pin "47") (pinfunction "GND_47") (pintype "bidirectional"))
      (node (ref "U1") (pin "5") (pinfunction "GND_5") (pintype "bidirectional"))
      (node (ref "U1") (pin "51") (pinfunction "GND_51") (pintype "bidirectional"))
      (node (ref "U1") (pin "TP") (pinfunction "GND_TP") (pintype "bidirectional"))
      (node (ref "U2") (pin "1") (pinfunction "GND_1") (pintype "bidirectional"))
      (node (ref "U3") (pin "3") (pinfunction "VSS_3") (pintype "power_in"))
      (node (ref "U4") (pin "11") (pinfunction "GND_11") (pintype "bidirectional"))
      (node (ref "U4") (pin "12") (pinfunction "GND_12") (pintype "bidirectional"))
      (node (ref "U4") (pin "13") (pinfunction "GND_13") (pintype "bidirectional"))
      (node (ref "U5") (pin "11") (pinfunction "GND_11") (pintype "bidirectional"))
      (node (ref "U5") (pin "12") (pinfunction "GND_12") (pintype "bidirectional"))
      (node (ref "U5") (pin "13") (pinfunction "GND_13") (pintype "bidirectional"))
      (node (ref "U6") (pin "2") (pinfunction "GND_2") (pintype "bidirectional"))
      (node (ref "U7") (pin "1") (pinfunction "GND_1") (pintype "bidirectional"))
      (node (ref "U8") (pin "7") (pinfunction "VSS_7") (pintype "bidirectional"))
      (node (ref "Y1") (pin "2") (pinfunction "CH_2") (pintype "bidirectional"))
      (node (ref "Y1") (pin "4") (pinfunction "CH_4") (pintype "bidirectional"))
    )
    (net (code "13") (name "1.8V") (class "Default")
      (node (ref "C14") (pin "1") (pinfunction "1_1") (pintype "passive"))
      (node (ref "C34") (pin "1") (pinfunction "+_1") (pintype "passive"))
      (node (ref "SW1") (pin "4") (pinfunction "NO2_4") (pintype "passive"))
      (node (ref "SW2") (pin "4") (pinfunction "NO2_4") (pintype "passive"))
      (node (ref "U2") (pin "2") (pinfunction "OUT_2") (pintype "bidirectional"))
      (node (ref "U2") (pin "4") (pinfunction "OUT_4") (pintype "bidirectional"))
    )
    (net (code "14") (name "3.3V") (class "Default")
      (node (ref "C1") (pin "1") (pinfunction "+_1") (pintype "passive"))
      (node (ref "C11") (pin "1") (pinfunction "1_1") (pintype "passive"))
      (node (ref "C12") (pin "1") (pinfunction "1_1") (pintype "passive"))
      (node (ref "C13") (pin "1") (pinfunction "1_1") (pintype "passive"))
      (node (ref "C15") (pin "1") (pinfunction "1_1") (pintype "passive"))
      (node (ref "C23") (pin "1") (pinfunction "1_1") (pintype "passive"))
      (node (ref "C24") (pin "1") (pinfunction "1_1") (pintype "passive"))
      (node (ref "C25") (pin "1") (pinfunction "1_1") (pintype "passive"))
      (node (ref "C26") (pin "1") (pinfunction "1_1") (pintype "passive"))
      (node (ref "C7") (pin "1") (pinfunction "1_1") (pintype "passive"))
      (node (ref "C8") (pin "1") (pinfunction "1_1") (pintype "passive"))
      (node (ref "FB2") (pin "1") (pinfunction "1_1") (pintype "passive"))
      (node (ref "FB3") (pin "1") (pinfunction "1_1") (pintype "passive"))
      (node (ref "R10") (pin "1") (pinfunction "1_1") (pintype "passive"))
      (node (ref "R11") (pin "1") (pinfunction "1_1") (pintype "passive"))
      (node (ref "R14") (pin "2") (pinfunction "2_2") (pintype "passive"))
      (node (ref "R16") (pin "2") (pinfunction "2_2") (pintype "passive"))
      (node (ref "R18") (pin "1") (pinfunction "1_1") (pintype "passive"))
      (node (ref "R19") (pin "2") (pinfunction "2_2") (pintype "passive"))
      (node (ref "R20") (pin "2") (pinfunction "2_2") (pintype "passive"))
      (node (ref "R4") (pin "1") (pinfunction "1_1") (pintype "passive"))
      (node (ref "R8") (pin "2") (pinfunction "2_2") (pintype "passive"))
      (node (ref "R9") (pin "1") (pinfunction "1_1") (pintype "passive"))
      (node (ref "RN1") (pin "1") (pinfunction "1_1") (pintype "passive"))
      (node (ref "RN1") (pin "2") (pinfunction "2_2") (pintype "passive"))
      (node (ref "RN1") (pin "3") (pinfunction "3_3") (pintype "passive"))
      (node (ref "RN1") (pin "4") (pinfunction "4_4") (pintype "passive"))
      (node (ref "RN1") (pin "5") (pinfunction "5_5") (pintype "passive"))
      (node (ref "RN1") (pin "6") (pinfunction "6_6") (pintype "passive"))
      (node (ref "RN1") (pin "7") (pinfunction "7_7") (pintype "passive"))
      (node (ref "RN1") (pin "8") (pinfunction "8_8") (pintype "passive"))
      (node (ref "SW1") (pin "2") (pinfunction "NO1_2") (pintype "passive"))
      (node (ref "SW2") (pin "2") (pinfunction "NO1_2") (pintype "passive"))
      (node (ref "U1") (pin "20") (pinfunction "VCCIO_20") (pintype "bidirectional"))
      (node (ref "U1") (pin "31") (pinfunction "VCCIO_31") (pintype "bidirectional"))
      (node (ref "U1") (pin "42") (pinfunction "VCCIO_42") (pintype "bidirectional"))
      (node (ref "U1") (pin "50") (pinfunction "VREGIN_50") (pintype "bidirectional"))
      (node (ref "U1") (pin "56") (pinfunction "VCCIO_56") (pintype "bidirectional"))
      (node (ref "U2") (pin "3") (pinfunction "IN_3") (pintype "bidirectional"))
      (node (ref "U4") (pin "1") (pinfunction "VCCA_1") (pintype "bidirectional"))
      (node (ref "U5") (pin "1") (pinfunction "VCCA_1") (pintype "bidirectional"))
      (node (ref "U6") (pin "6") (pinfunction "VDD_6") (pintype "bidirectional"))
      (node (ref "U7") (pin "2") (pinfunction "OUT_2") (pintype "bidirectional"))
      (node (ref "U7") (pin "4") (pinfunction "OUT_4") (pintype "bidirectional"))
    )
    (net (code "15") (name "5V") (class "Default")
      (node (ref "C2") (pin "1") (pinfunction "+_1") (pintype "passive"))
      (node (ref "C3") (pin "1") (pinfunction "1_1") (pintype "passive"))
      (node (ref "FB1") (pin "2") (pinfunction "2_2") (pintype "passive"))
      (node (ref "SW1") (pin "1") (pinfunction "NC_1") (pintype "passive"))
      (node (ref "SW2") (pin "1") (pinfunction "NC_1") (pintype "passive"))
      (node (ref "U7") (pin "3") (pinfunction "IN_3") (pintype "bidirectional"))
    )
    (net (code "16") (name "AD0") (class "Default")
      (node (ref "JP3") (pin "3") (pinfunction "3_3") (pintype "passive"))
      (node (ref "JP4") (pin "7") (pinfunction "7_7") (pintype "passive"))
      (node (ref "R29") (pin "1") (pinfunction "1_1") (pintype "passive"))
      (node (ref "RN2") (pin "9") (pinfunction "9_9") (pintype "passive"))
    )
    (net (code "17") (name "AD1") (class "Default")
      (node (ref "JP3") (pin "4") (pinfunction "4_4") (pintype "passive"))
      (node (ref "JP4") (pin "8") (pinfunction "8_8") (pintype "passive"))
      (node (ref "R23") (pin "1") (pinfunction "1_1") (pintype "passive"))
      (node (ref "R28") (pin "1") (pinfunction "1_1") (pintype "passive"))
      (node (ref "RN5") (pin "16") (pinfunction "16_16") (pintype "passive"))
      (node (ref "U5") (pin "21") (pinfunction "B1_21") (pintype "bidirectional"))
    )
    (net (code "18") (name "AD2") (class "Default")
      (node (ref "JP3") (pin "5") (pinfunction "5_5") (pintype "passive"))
      (node (ref "Q3") (pin "2") (pinfunction "E_2") (pintype "passive"))
      (node (ref "R27") (pin "1") (pinfunction "1_1") (pintype "passive"))
      (node (ref "RN2") (pin "10") (pinfunction "10_10") (pintype "passive"))
    )
    (net (code "19") (name "AD3") (class "Default")
      (node (ref "JP3") (pin "6") (pinfunction "6_6") (pintype "passive"))
      (node (ref "RN5") (pin "15") (pinfunction "15_15") (pintype "passive"))
      (node (ref "U5") (pin "20") (pinfunction "B2_20") (pintype "bidirectional"))
    )
    (net (code "20") (name "AD4") (class "Default")
      (node (ref "JP3") (pin "7") (pinfunction "7_7") (pintype "passive"))
      (node (ref "Q4") (pin "2") (pinfunction "E_2") (pintype "passive"))
      (node (ref "R26") (pin "1") (pinfunction "1_1") (pintype "passive"))
      (node (ref "RN2") (pin "11") (pinfunction "11_11") (pintype "passive"))
    )
    (net (code "21") (name "AD5") (class "Default")
      (node (ref "JP3") (pin "8") (pinfunction "8_8") (pintype "passive"))
      (node (ref "RN5") (pin "14") (pinfunction "14_14") (pintype "passive"))
      (node (ref "U5") (pin "19") (pinfunction "B3_19") (pintype "bidirectional"))
    )
    (net (code "22") (name "AD6") (class "Default")
      (node (ref "JP3") (pin "9") (pinfunction "9_9") (pintype "passive"))
      (node (ref "RN5") (pin "13") (pinfunction "13_13") (pintype "passive"))
      (node (ref "U5") (pin "18") (pinfunction "B4_18") (pintype "bidirectional"))
    )
    (net (code "23") (name "ADBUS0") (class "Default")
      (node (ref "RN1") (pin "9") (pinfunction "9_9") (pintype "passive"))
      (node (ref "RN5") (pin "9") (pinfunction "9_9") (pintype "passive"))
      (node (ref "U1") (pin "16") (pinfunction "ADBUS0_16") (pintype "bidirectional"))
      (node (ref "U4") (pin "10") (pinfunction "A8_10") (pintype "bidirectional"))
      (node (ref "U5") (pin "14") (pinfunction "B8_14") (pintype "bidirectional"))
    )
    (net (code "24") (name "ADBUS1") (class "Default")
      (node (ref "RN4") (pin "1") (pinfunction "1_1") (pintype "passive"))
      (node (ref "U1") (pin "17") (pinfunction "ADBUS1_17") (pintype "bidirectional"))
    )
    (net (code "25") (name "ADBUS2") (class "Default")
      (node (ref "RN1") (pin "10") (pinfunction "10_10") (pintype "passive"))
      (node (ref "RN5") (pin "10") (pinfunction "10_10") (pintype "passive"))
      (node (ref "U1") (pin "18") (pinfunction "ADBUS2_18") (pintype "bidirectional"))
      (node (ref "U4") (pin "9") (pinfunction "A7_9") (pintype "bidirectional"))
      (node (ref "U5") (pin "15") (pinfunction "B7_15") (pintype "bidirectional"))
    )
    (net (code "26") (name "ADBUS3") (class "Default")
      (node (ref "RN4") (pin "2") (pinfunction "2_2") (pintype "passive"))
      (node (ref "U1") (pin "19") (pinfunction "ADBUS3_19") (pintype "bidirectional"))
    )
    (net (code "27") (name "ADBUS4") (class "Default")
      (node (ref "RN1") (pin "11") (pinfunction "11_11") (pintype "passive"))
      (node (ref "U1") (pin "21") (pinfunction "ADBUS4_21") (pintype "bidirectional"))
      (node (ref "U4") (pin "8") (pinfunction "A6_8") (pintype "bidirectional"))
    )
    (net (code "28") (name "ADBUS5") (class "Default")
      (node (ref "RN4") (pin "3") (pinfunction "3_3") (pintype "passive"))
      (node (ref "U1") (pin "22") (pinfunction "ADBUS5_22") (pintype "bidirectional"))
    )
    (net (code "29") (name "ADBUS6") (class "Default")
      (node (ref "RN4") (pin "4") (pinfunction "4_4") (pintype "passive"))
      (node (ref "U1") (pin "23") (pinfunction "ADBUS6_23") (pintype "bidirectional"))
    )
    (net (code "30") (name "ADBUS7") (class "Default")
      (node (ref "U1") (pin "24") (pinfunction "ADBUS7_24") (pintype "bidirectional"))
    )
    (net (code "31") (name "BD0") (class "Default")
      (node (ref "CN2") (pin "4") (pinfunction "TCK_4") (pintype "bidirectional"))
      (node (ref "CN3") (pin "4") (pinfunction "4_4") (pintype "passive"))
      (node (ref "JP1") (pin "3") (pinfunction "3_3") (pintype "passive"))
      (node (ref "JP2") (pin "6") (pinfunction "6_6") (pintype "passive"))
      (node (ref "JP4") (pin "1") (pinfunction "1_1") (pintype "passive"))
      (node (ref "JP5") (pin "3") (pinfunction "3_3") (pintype "passive"))
      (node (ref "RN2") (pin "16") (pinfunction "16_16") (pintype "passive"))
      (node (ref "U8") (pin "12") (pinfunction "A_12") (pintype "bidirectional"))
    )
    (net (code "32") (name "BD1") (class "Default")
      (node (ref "CN2") (pin "8") (pinfunction "TDI_8") (pintype "bidirectional"))
      (node (ref "CN3") (pin "3") (pinfunction "3_3") (pintype "passive"))
      (node (ref "JP1") (pin "4") (pinfunction "4_4") (pintype "passive"))
      (node (ref "JP2") (pin "8") (pinfunction "8_8") (pintype "passive"))
      (node (ref "JP4") (pin "2") (pinfunction "2_2") (pintype "passive"))
      (node (ref "R22") (pin "2") (pinfunction "2_2") (pintype "passive"))
      (node (ref "RN2") (pin "15") (pinfunction "15_15") (pintype "passive"))
      (node (ref "SJ1") (pin "2") (pinfunction "3_2") (pintype "passive"))
      (node (ref "U8") (pin "9") (pinfunction "A_9") (pintype "bidirectional"))
    )
    (net (code "33") (name "BD2") (class "Default")
      (node (ref "JP4") (pin "3") (pinfunction "3_3") (pintype "passive"))
      (node (ref "RN5") (pin "12") (pinfunction "12_12") (pintype "passive"))
      (node (ref "SW3") (pin "5") (pinfunction "C_5") (pintype "passive"))
      (node (ref "U5") (pin "17") (pinfunction "B5_17") (pintype "bidirectional"))
    )
    (net (code "34") (name "BD2_EXT_SWITCHED") (class "Default")
      (node (ref "CN2") (pin "6") (pinfunction "TDO_6") (pintype "bidirectional"))
      (node (ref "JP1") (pin "5") (pinfunction "5_5") (pintype "passive"))
      (node (ref "JP2") (pin "3") (pinfunction "3_3") (pintype "passive"))
      (node (ref "JP5") (pin "1") (pinfunction "1_1") (pintype "passive"))
      (node (ref "SW3") (pin "4") (pinfunction "NC_4") (pintype "passive"))
      (node (ref "U8") (pin "6") (pinfunction "Y_6") (pintype "bidirectional"))
    )
    (net (code "35") (name "BD3") (class "Default")
      (node (ref "JP1") (pin "6") (pinfunction "6_6") (pintype "passive"))
      (node (ref "JP2") (pin "1") (pinfunction "1_1") (pintype "passive"))
      (node (ref "JP4") (pin "4") (pinfunction "4_4") (pintype "passive"))
      (node (ref "RN2") (pin "14") (pinfunction "14_14") (pintype "passive"))
      (node (ref "SW3") (pin "1") (pinfunction "NC_1") (pintype "passive"))
      (node (ref "U8") (pin "2") (pinfunction "A_2") (pintype "bidirectional"))
    )
    (net (code "36") (name "BD4") (class "Default")
      (node (ref "JP1") (pin "7") (pinfunction "7_7") (pintype "passive"))
      (node (ref "JP4") (pin "5") (pinfunction "5_5") (pintype "passive"))
      (node (ref "RN2") (pin "13") (pinfunction "13_13") (pintype "passive"))
    )
    (net (code "37") (name "BD5") (class "Default")
      (node (ref "CN2") (pin "10") (pinfunction "~{RST}_10") (pintype "bidirectional"))
      (node (ref "JP1") (pin "8") (pinfunction "8_8") (pintype "passive"))
      (node (ref "JP4") (pin "6") (pinfunction "6_6") (pintype "passive"))
      (node (ref "JP5") (pin "5") (pinfunction "5_5") (pintype "passive"))
      (node (ref "RN2") (pin "12") (pinfunction "12_12") (pintype "passive"))
    )
    (net (code "38") (name "BD6") (class "Default")
      (node (ref "JP1") (pin "9") (pinfunction "9_9") (pintype "passive"))
      (node (ref "R23") (pin "2") (pinfunction "2_2") (pintype "passive"))
      (node (ref "RN5") (pin "11") (pinfunction "11_11") (pintype "passive"))
      (node (ref "U5") (pin "16") (pinfunction "B6_16") (pintype "bidirectional"))
    )
    (net (code "39") (name "BDBUS0") (class "Default")
      (node (ref "RN1") (pin "16") (pinfunction "16_16") (pintype "passive"))
      (node (ref "U1") (pin "38") (pinfunction "BDBUS0_38") (pintype "bidirectional"))
      (node (ref "U4") (pin "3") (pinfunction "A1_3") (pintype "bidirectional"))
    )
    (net (code "40") (name "BDBUS1") (class "Default")
      (node (ref "RN1") (pin "15") (pinfunction "15_15") (pintype "passive"))
      (node (ref "U1") (pin "39") (pinfunction "BDBUS1_39") (pintype "bidirectional"))
      (node (ref "U4") (pin "4") (pinfunction "A2_4") (pintype "bidirectional"))
    )
    (net (code "41") (name "BDBUS2") (class "Default")
      (node (ref "RN4") (pin "5") (pinfunction "5_5") (pintype "passive"))
      (node (ref "U1") (pin "40") (pinfunction "BDBUS2_40") (pintype "bidirectional"))
    )
    (net (code "42") (name "BDBUS3") (class "Default")
      (node (ref "RN1") (pin "14") (pinfunction "14_14") (pintype "passive"))
      (node (ref "U1") (pin "41") (pinfunction "BDBUS3_41") (pintype "bidirectional"))
      (node (ref "U4") (pin "5") (pinfunction "A3_5") (pintype "bidirectional"))
    )
    (net (code "43") (name "BDBUS4") (class "Default")
      (node (ref "RN1") (pin "13") (pinfunction "13_13") (pintype "passive"))
      (node (ref "U1") (pin "43") (pinfunction "BDBUS4_43") (pintype "bidirectional"))
      (node (ref "U4") (pin "6") (pinfunction "A4_6") (pintype "bidirectional"))
    )
    (net (code "44") (name "BDBUS5") (class "Default")
      (node (ref "R21") (pin "1") (pinfunction "1_1") (pintype "passive"))
      (node (ref "RN1") (pin "12") (pinfunction "12_12") (pintype "passive"))
      (node (ref "U1") (pin "44") (pinfunction "BDBUS5_44") (pintype "bidirectional"))
      (node (ref "U4") (pin "7") (pinfunction "A5_7") (pintype "bidirectional"))
    )
    (net (code "45") (name "BDBUS6") (class "Default")
      (node (ref "RN4") (pin "6") (pinfunction "6_6") (pintype "passive"))
      (node (ref "U1") (pin "45") (pinfunction "BDBUS6_45") (pintype "bidirectional"))
    )
    (net (code "46") (name "BDBUS7") (class "Default")
      (node (ref "R21") (pin "2") (pinfunction "2_2") (pintype "passive"))
      (node (ref "U1") (pin "46") (pinfunction "BDBUS7_46") (pintype "bidirectional"))
    )
    (net (code "47") (name "Net-(CN1-CC1)") (class "Default")
      (node (ref "CN1") (pin "A5") (pinfunction "CC1_A5") (pintype "bidirectional"))
      (node (ref "R3") (pin "2") (pinfunction "2_2") (pintype "passive"))
    )
    (net (code "48") (name "Net-(CN1-CC2)") (class "Default")
      (node (ref "CN1") (pin "B5") (pinfunction "CC2_B5") (pintype "bidirectional"))
      (node (ref "R1") (pin "2") (pinfunction "2_2") (pintype "passive"))
    )
    (net (code "49") (name "Net-(CN2-TMS)") (class "Default")
      (node (ref "CN2") (pin "2") (pinfunction "TMS_2") (pintype "bidirectional"))
      (node (ref "SW3") (pin "2") (pinfunction "C_2") (pintype "passive"))
    )
    (net (code "50") (name "Net-(D1-VCC)") (class "Default")
      (node (ref "D1") (pin "5") (pinfunction "VCC_5") (pintype "power_in"))
      (node (ref "D4") (pin "2") (pinfunction "A_2") (pintype "passive"))
      (node (ref "R34") (pin "2") (pinfunction "2_2") (pintype "passive"))
      (node (ref "R7") (pin "2") (pinfunction "2_2") (pintype "passive"))
      (node (ref "RT1") (pin "1") (pinfunction "1_1") (pintype "passive"))
    )
    (net (code "51") (name "Net-(D2-A)") (class "Default")
      (node (ref "D2") (pin "2") (pinfunction "A_2") (pintype "passive"))
      (node (ref "R33") (pin "1") (pinfunction "1_1") (pintype "passive"))
      (node (ref "U3") (pin "4") (pinfunction "Y_4") (pintype "bidirectional"))
    )
    (net (code "52") (name "Net-(D4-K)") (class "Default")
      (node (ref "D4") (pin "1") (pinfunction "K_1") (pintype "passive"))
      (node (ref "FB1") (pin "1") (pinfunction "1_1") (pintype "passive"))
    )
    (net (code "53") (name "Net-(D6-K)") (class "Default")
      (node (ref "C4") (pin "2") (pinfunction "2_2") (pintype "passive"))
      (node (ref "D6") (pin "1") (pinfunction "K_1") (pintype "passive"))
      (node (ref "M6") (pin "1") (pinfunction "G_1") (pintype "passive"))
      (node (ref "R32") (pin "2") (pinfunction "2_2") (pintype "passive"))
    )
    (net (code "54") (name "Net-(JP2-Pad4)") (class "Default")
      (node (ref "JP2") (pin "4") (pinfunction "4_4") (pintype "passive"))
      (node (ref "R24") (pin "1") (pinfunction "1_1") (pintype "passive"))
    )
    (net (code "55") (name "Net-(JP2-Pad5)") (class "Default")
      (node (ref "JP2") (pin "5") (pinfunction "5_5") (pintype "passive"))
      (node (ref "R25") (pin "1") (pinfunction "1_1") (pintype "passive"))
    )
    (net (code "56") (name "Net-(LED1-PadA)") (class "Default")
      (node (ref "LED1") (pin "A") (pinfunction "A_A") (pintype "passive"))
      (node (ref "R7") (pin "1") (pinfunction "1_1") (pintype "passive"))
    )
    (net (code "57") (name "Net-(LED2-PadA)") (class "Default")
      (node (ref "LED2") (pin "A") (pinfunction "A_A") (pintype "passive"))
      (node (ref "R8") (pin "1") (pinfunction "1_1") (pintype "passive"))
    )
    (net (code "58") (name "Net-(LED3-PadA)") (class "Default")
      (node (ref "LED3") (pin "A") (pinfunction "A_A") (pintype "passive"))
      (node (ref "R16") (pin "1") (pinfunction "1_1") (pintype "passive"))
    )
    (net (code "59") (name "Net-(LED4-PadA)") (class "Default")
      (node (ref "LED4") (pin "A") (pinfunction "A_A") (pintype "passive"))
      (node (ref "R19") (pin "1") (pinfunction "1_1") (pintype "passive"))
    )
    (net (code "60") (name "Net-(LED5-PadA)") (class "Default")
      (node (ref "LED5") (pin "A") (pinfunction "A_A") (pintype "passive"))
      (node (ref "R20") (pin "1") (pinfunction "1_1") (pintype "passive"))
    )
    (net (code "61") (name "Net-(M1-D)") (class "Default")
      (node (ref "LED2") (pin "K") (pinfunction "K_K") (pintype "passive"))
      (node (ref "M1") (pin "3") (pinfunction "D_3") (pintype "passive"))
    )
    (net (code "62") (name "Net-(M1-G)") (class "Default")
      (node (ref "M1") (pin "1") (pinfunction "G_1") (pintype "passive"))
      (node (ref "R15") (pin "2") (pinfunction "2_2") (pintype "passive"))
    )
    (net (code "63") (name "Net-(M2-D)") (class "Default")
      (node (ref "LED3") (pin "K") (pinfunction "K_K") (pintype "passive"))
      (node (ref "M2") (pin "3") (pinfunction "D_3") (pintype "passive"))
    )
    (net (code "64") (name "Net-(M2-G)") (class "Default")
      (node (ref "M2") (pin "1") (pinfunction "G_1") (pintype "passive"))
      (node (ref "R17") (pin "2") (pinfunction "2_2") (pintype "passive"))
    )
    (net (code "65") (name "Net-(M6-D)") (class "Default")
      (node (ref "C33") (pin "1") (pinfunction "1_1") (pintype "passive"))
      (node (ref "M6") (pin "3") (pinfunction "D_3") (pintype "passive"))
      (node (ref "U3") (pin "5") (pinfunction "VDD_5") (pintype "power_in"))
      (node (ref "U8") (pin "14") (pinfunction "VDD_14") (pintype "bidirectional"))
    )
    (net (code "66") (name "Net-(Q3-B)") (class "Default")
      (node (ref "Q3") (pin "1") (pinfunction "B_1") (pintype "passive"))
      (node (ref "R26") (pin "2") (pinfunction "2_2") (pintype "passive"))
    )
    (net (code "67") (name "Net-(Q4-B)") (class "Default")
      (node (ref "Q4") (pin "1") (pinfunction "B_1") (pintype "passive"))
      (node (ref "R27") (pin "2") (pinfunction "2_2") (pintype "passive"))
    )
    (net (code "68") (name "Net-(SW3A-NO)") (class "Default")
      (node (ref "R22") (pin "1") (pinfunction "1_1") (pintype "passive"))
      (node (ref "SJ1") (pin "1") (pinfunction "1_1") (pintype "passive"))
      (node (ref "SW3") (pin "3") (pinfunction "NO_3") (pintype "passive"))
      (node (ref "SW3") (pin "6") (pinfunction "NO_6") (pintype "passive"))
    )
    (net (code "69") (name "Net-(U1-ACBUS3)") (class "Default")
      (node (ref "LED4") (pin "K") (pinfunction "K_K") (pintype "passive"))
      (node (ref "U1") (pin "29") (pinfunction "ACBUS3_29") (pintype "bidirectional"))
    )
    (net (code "70") (name "Net-(U1-ACBUS4)") (class "Default")
      (node (ref "LED5") (pin "K") (pinfunction "K_K") (pintype "passive"))
      (node (ref "U1") (pin "30") (pinfunction "ACBUS4_30") (pintype "bidirectional"))
    )
    (net (code "71") (name "Net-(U1-EECLK)") (class "Default")
      (node (ref "R10") (pin "2") (pinfunction "2_2") (pintype "passive"))
      (node (ref "U1") (pin "62") (pinfunction "EECLK_62") (pintype "bidirectional"))
      (node (ref "U6") (pin "4") (pinfunction "CLK_4") (pintype "bidirectional"))
    )
    (net (code "72") (name "Net-(U1-EECS)") (class "Default")
      (node (ref "R9") (pin "2") (pinfunction "2_2") (pintype "passive"))
      (node (ref "U1") (pin "63") (pinfunction "EECS_63") (pintype "bidirectional"))
      (node (ref "U6") (pin "5") (pinfunction "CS_5") (pintype "bidirectional"))
    )
    (net (code "73") (name "Net-(U1-EEDATA)") (class "Default")
      (node (ref "R12") (pin "1") (pinfunction "1_1") (pintype "passive"))
      (node (ref "U1") (pin "61") (pinfunction "EEDATA_61") (pintype "bidirectional"))
      (node (ref "U6") (pin "3") (pinfunction "DI_3") (pintype "bidirectional"))
    )
    (net (code "74") (name "Net-(U1-OSCI)") (class "Default")
      (node (ref "C16") (pin "1") (pinfunction "1_1") (pintype "passive"))
      (node (ref "U1") (pin "2") (pinfunction "OSCI_2") (pintype "bidirectional"))
      (node (ref "Y1") (pin "1") (pinfunction "IN_1") (pintype "passive"))
    )
    (net (code "75") (name "Net-(U1-OSCO)") (class "Default")
      (node (ref "C17") (pin "1") (pinfunction "1_1") (pintype "passive"))
      (node (ref "U1") (pin "3") (pinfunction "OSCO_3") (pintype "bidirectional"))
      (node (ref "Y1") (pin "3") (pinfunction "OUT_3") (pintype "passive"))
    )
    (net (code "76") (name "Net-(U1-REF)") (class "Default")
      (node (ref "R13") (pin "1") (pinfunction "1_1") (pintype "passive"))
      (node (ref "U1") (pin "6") (pinfunction "REF_6") (pintype "bidirectional"))
    )
    (net (code "77") (name "Net-(U1-VPHY)") (class "Default")
      (node (ref "C27") (pin "1") (pinfunction "1_1") (pintype "passive"))
      (node (ref "C28") (pin "1") (pinfunction "1_1") (pintype "passive"))
      (node (ref "FB2") (pin "2") (pinfunction "2_2") (pintype "passive"))
      (node (ref "U1") (pin "4") (pinfunction "VPHY_4") (pintype "bidirectional"))
    )
    (net (code "78") (name "Net-(U1-VPLL)") (class "Default")
      (node (ref "C29") (pin "1") (pinfunction "1_1") (pintype "passive"))
      (node (ref "C30") (pin "1") (pinfunction "1_1") (pintype "passive"))
      (node (ref "FB3") (pin "2") (pinfunction "2_2") (pintype "passive"))
      (node (ref "U1") (pin "9") (pinfunction "VPLL_9") (pintype "bidirectional"))
    )
    (net (code "79") (name "Net-(U1-~{RESET})") (class "Default")
      (node (ref "R14") (pin "1") (pinfunction "1_1") (pintype "passive"))
      (node (ref "U1") (pin "14") (pinfunction "~{RESET}_14") (pintype "bidirectional"))
    )
    (net (code "80") (name "Net-(U4-B1)") (class "Default")
      (node (ref "RN2") (pin "1") (pinfunction "1_1") (pintype "passive"))
      (node (ref "U4") (pin "21") (pinfunction "B1_21") (pintype "bidirectional"))
    )
    (net (code "81") (name "Net-(U4-B2)") (class "Default")
      (node (ref "RN2") (pin "2") (pinfunction "2_2") (pintype "passive"))
      (node (ref "U4") (pin "20") (pinfunction "B2_20") (pintype "bidirectional"))
    )
    (net (code "82") (name "Net-(U4-B3)") (class "Default")
      (node (ref "RN2") (pin "3") (pinfunction "3_3") (pintype "passive"))
      (node (ref "U4") (pin "19") (pinfunction "B3_19") (pintype "bidirectional"))
    )
    (net (code "83") (name "Net-(U4-B4)") (class "Default")
      (node (ref "RN2") (pin "4") (pinfunction "4_4") (pintype "passive"))
      (node (ref "U4") (pin "18") (pinfunction "B4_18") (pintype "bidirectional"))
    )
    (net (code "84") (name "Net-(U4-B5)") (class "Default")
      (node (ref "RN2") (pin "5") (pinfunction "5_5") (pintype "passive"))
      (node (ref "U4") (pin "17") (pinfunction "B5_17") (pintype "bidirectional"))
    )
    (net (code "85") (name "Net-(U4-B6)") (class "Default")
      (node (ref "RN2") (pin "6") (pinfunction "6_6") (pintype "passive"))
      (node (ref "U4") (pin "16") (pinfunction "B6_16") (pintype "bidirectional"))
    )
    (net (code "86") (name "Net-(U4-B7)") (class "Default")
      (node (ref "RN2") (pin "7") (pinfunction "7_7") (pintype "passive"))
      (node (ref "U4") (pin "15") (pinfunction "B7_15") (pintype "bidirectional"))
    )
    (net (code "87") (name "Net-(U4-B8)") (class "Default")
      (node (ref "RN2") (pin "8") (pinfunction "8_8") (pintype "passive"))
      (node (ref "U4") (pin "14") (pinfunction "B8_14") (pintype "bidirectional"))
    )
    (net (code "88") (name "Net-(U4-DIR)") (class "Default")
      (node (ref "R4") (pin "2") (pinfunction "2_2") (pintype "passive"))
      (node (ref "U4") (pin "2") (pinfunction "DIR_2") (pintype "bidirectional"))
    )
    (net (code "89") (name "Net-(U5-A1)") (class "Default")
      (node (ref "RN4") (pin "16") (pinfunction "16_16") (pintype "passive"))
      (node (ref "U5") (pin "3") (pinfunction "A1_3") (pintype "bidirectional"))
    )
    (net (code "90") (name "Net-(U5-A2)") (class "Default")
      (node (ref "RN4") (pin "15") (pinfunction "15_15") (pintype "passive"))
      (node (ref "U5") (pin "4") (pinfunction "A2_4") (pintype "bidirectional"))
    )
    (net (code "91") (name "Net-(U5-A3)") (class "Default")
      (node (ref "RN4") (pin "14") (pinfunction "14_14") (pintype "passive"))
      (node (ref "U5") (pin "5") (pinfunction "A3_5") (pintype "bidirectional"))
    )
    (net (code "92") (name "Net-(U5-A4)") (class "Default")
      (node (ref "RN4") (pin "13") (pinfunction "13_13") (pintype "passive"))
      (node (ref "U5") (pin "6") (pinfunction "A4_6") (pintype "bidirectional"))
    )
    (net (code "93") (name "Net-(U5-A5)") (class "Default")
      (node (ref "RN4") (pin "12") (pinfunction "12_12") (pintype "passive"))
      (node (ref "U5") (pin "7") (pinfunction "A5_7") (pintype "bidirectional"))
    )
    (net (code "94") (name "Net-(U5-A6)") (class "Default")
      (node (ref "RN4") (pin "11") (pinfunction "11_11") (pintype "passive"))
      (node (ref "U5") (pin "8") (pinfunction "A6_8") (pintype "bidirectional"))
    )
    (net (code "95") (name "Net-(U5-A7)") (class "Default")
      (node (ref "RN4") (pin "10") (pinfunction "10_10") (pintype "passive"))
      (node (ref "U5") (pin "9") (pinfunction "A7_9") (pintype "bidirectional"))
    )
    (net (code "96") (name "Net-(U5-A8)") (class "Default")
      (node (ref "RN4") (pin "9") (pinfunction "9_9") (pintype "passive"))
      (node (ref "U5") (pin "10") (pinfunction "A8_10") (pintype "bidirectional"))
    )
    (net (code "97") (name "Net-(U5-DIR)") (class "Default")
      (node (ref "R5") (pin "1") (pinfunction "1_1") (pintype "passive"))
      (node (ref "U5") (pin "2") (pinfunction "DIR_2") (pintype "bidirectional"))
    )
    (net (code "98") (name "Net-(U6-DO)") (class "Default")
      (node (ref "R11") (pin "2") (pinfunction "2_2") (pintype "passive"))
      (node (ref "R12") (pin "2") (pinfunction "2_2") (pintype "passive"))
      (node (ref "U6") (pin "1") (pinfunction "DO_1") (pintype "bidirectional"))
    )
    (net (code "99") (name "USB_D+") (class "Default")
      (node (ref "CN1") (pin "A6") (pinfunction "D+_A6") (pintype "bidirectional"))
      (node (ref "CN1") (pin "B6") (pinfunction "D+_B6") (pintype "bidirectional"))
      (node (ref "D1") (pin "1") (pinfunction "IO1_1") (pintype "bidirectional"))
      (node (ref "D1") (pin "6") (pinfunction "IO1_6") (pintype "bidirectional"))
      (node (ref "U1") (pin "8") (pinfunction "DP_8") (pintype "bidirectional"))
    )
    (net (code "100") (name "USB_D-") (class "Default")
      (node (ref "CN1") (pin "A7") (pinfunction "D-_A7") (pintype "bidirectional"))
      (node (ref "CN1") (pin "B7") (pinfunction "D-_B7") (pintype "bidirectional"))
      (node (ref "D1") (pin "3") (pinfunction "IO2_3") (pintype "bidirectional"))
      (node (ref "D1") (pin "4") (pinfunction "IO2_4") (pintype "bidirectional"))
      (node (ref "U1") (pin "7") (pinfunction "DM_7") (pintype "bidirectional"))
    )
    (net (code "101") (name "VBUS") (class "Default")
      (node (ref "CN1") (pin "A4_B9") (pinfunction "VBUS_A4_B9") (pintype "bidirectional"))
      (node (ref "CN1") (pin "B4_A9") (pinfunction "VBUS_B4_A9") (pintype "bidirectional"))
      (node (ref "RT1") (pin "2") (pinfunction "2_2") (pintype "passive"))
    )
    (net (code "102") (name "VLOGIC") (class "Default")
      (node (ref "C10") (pin "1") (pinfunction "1_1") (pintype "passive"))
      (node (ref "C4") (pin "1") (pinfunction "1_1") (pintype "passive"))
      (node (ref "C5") (pin "1") (pinfunction "1_1") (pintype "passive"))
      (node (ref "C6") (pin "1") (pinfunction "1_1") (pintype "passive"))
      (node (ref "C9") (pin "1") (pinfunction "1_1") (pintype "passive"))
      (node (ref "M6") (pin "2") (pinfunction "S_2") (pintype "passive"))
      (node (ref "R2") (pin "2") (pinfunction "2_2") (pintype "passive"))
      (node (ref "R30") (pin "2") (pinfunction "2_2") (pintype "passive"))
      (node (ref "R31") (pin "2") (pinfunction "2_2") (pintype "passive"))
      (node (ref "RN5") (pin "1") (pinfunction "1_1") (pintype "passive"))
      (node (ref "RN5") (pin "2") (pinfunction "2_2") (pintype "passive"))
      (node (ref "RN5") (pin "3") (pinfunction "3_3") (pintype "passive"))
      (node (ref "RN5") (pin "4") (pinfunction "4_4") (pintype "passive"))
      (node (ref "RN5") (pin "5") (pinfunction "5_5") (pintype "passive"))
      (node (ref "RN5") (pin "6") (pinfunction "6_6") (pintype "passive"))
      (node (ref "RN5") (pin "7") (pinfunction "7_7") (pintype "passive"))
      (node (ref "RN5") (pin "8") (pinfunction "8_8") (pintype "passive"))
      (node (ref "SW1") (pin "3") (pinfunction "C_3") (pintype "passive"))
      (node (ref "U4") (pin "23") (pinfunction "VCCB_23") (pintype "bidirectional"))
      (node (ref "U4") (pin "24") (pinfunction "VCCB_24") (pintype "bidirectional"))
      (node (ref "U5") (pin "23") (pinfunction "VCCB_23") (pintype "bidirectional"))
      (node (ref "U5") (pin "24") (pinfunction "VCCB_24") (pintype "bidirectional"))
    )
    (net (code "103") (name "VTARGET") (class "Default")
      (node (ref "CN2") (pin "1") (pinfunction "VDD_1") (pintype "bidirectional"))
      (node (ref "CN3") (pin "2") (pinfunction "2_2") (pintype "passive"))
      (node (ref "CN4") (pin "1") (pinfunction "VDD_1") (pintype "bidirectional"))
      (node (ref "CN5") (pin "1") (pinfunction "1_1") (pintype "passive"))
      (node (ref "CN6") (pin "2") (pinfunction "2_2") (pintype "passive"))
      (node (ref "JP1") (pin "1") (pinfunction "1_1") (pintype "passive"))
      (node (ref "JP2") (pin "2") (pinfunction "2_2") (pintype "passive"))
      (node (ref "JP3") (pin "1") (pinfunction "1_1") (pintype "passive"))
      (node (ref "R15") (pin "1") (pinfunction "1_1") (pintype "passive"))
      (node (ref "R24") (pin "2") (pinfunction "2_2") (pintype "passive"))
      (node (ref "R25") (pin "2") (pinfunction "2_2") (pintype "passive"))
      (node (ref "R6") (pin "2") (pinfunction "2_2") (pintype "passive"))
      (node (ref "SW1") (pin "5") (pinfunction "NO3_5") (pintype "passive"))
      (node (ref "SW2") (pin "3") (pinfunction "C_3") (pintype "passive"))
    )
    (net (code "104") (name "unconnected-(CN2-Pad7)") (class "Default")
      (node (ref "CN2") (pin "7") (pinfunction "7_7") (pintype "bidirectional"))
    )
    (net (code "105") (name "unconnected-(CN4-Pad7)") (class "Default")
      (node (ref "CN4") (pin "7") (pinfunction "7_7") (pintype "bidirectional"))
    )
    (net (code "106") (name "unconnected-(CN4-~{RST}-Pad10)") (class "Default")
      (node (ref "CN4") (pin "10") (pinfunction "~{RST}_10") (pintype "bidirectional"))
    )
    (net (code "107") (name "unconnected-(CN5-Pad7)") (class "Default")
      (node (ref "CN5") (pin "7") (pinfunction "7_7") (pintype "passive"))
    )
    (net (code "108") (name "unconnected-(CN5-Pad10)") (class "Default")
      (node (ref "CN5") (pin "10") (pinfunction "10_10") (pintype "passive"))
    )
    (net (code "109") (name "unconnected-(JP4-Pad11)") (class "Default")
      (node (ref "JP4") (pin "11") (pinfunction "11_11") (pintype "passive"))
    )
    (net (code "110") (name "unconnected-(JP4-Pad12)") (class "Default")
      (node (ref "JP4") (pin "12") (pinfunction "12_12") (pintype "passive"))
    )
    (net (code "111") (name "unconnected-(JP4-Pad13)") (class "Default")
      (node (ref "JP4") (pin "13") (pinfunction "13_13") (pintype "passive"))
    )
    (net (code "112") (name "unconnected-(JP4-Pad14)") (class "Default")
      (node (ref "JP4") (pin "14") (pinfunction "14_14") (pintype "passive"))
    )
    (net (code "113") (name "unconnected-(JP5-Pad2)") (class "Default")
      (node (ref "JP5") (pin "2") (pinfunction "2_2") (pintype "passive"))
    )
    (net (code "114") (name "unconnected-(JP5-Pad4)") (class "Default")
      (node (ref "JP5") (pin "4") (pinfunction "4_4") (pintype "passive"))
    )
    (net (code "115") (name "unconnected-(JP5-Pad6)") (class "Default")
      (node (ref "JP5") (pin "6") (pinfunction "6_6") (pintype "passive"))
    )
    (net (code "116") (name "unconnected-(RN4-Pad7)") (class "Default")
      (node (ref "RN4") (pin "7") (pinfunction "7_7") (pintype "passive"))
    )
    (net (code "117") (name "unconnected-(RN4-Pad8)") (class "Default")
      (node (ref "RN4") (pin "8") (pinfunction "8_8") (pintype "passive"))
    )
    (net (code "118") (name "unconnected-(SW2A-NO3-Pad5)") (class "Default")
      (node (ref "SW2") (pin "5") (pinfunction "NO3_5") (pintype "passive"))
    )
    (net (code "119") (name "unconnected-(U1-ACBUS0-Pad26)") (class "Default")
      (node (ref "U1") (pin "26") (pinfunction "ACBUS0_26") (pintype "bidirectional"))
    )
    (net (code "120") (name "unconnected-(U1-ACBUS1-Pad27)") (class "Default")
      (node (ref "U1") (pin "27") (pinfunction "ACBUS1_27") (pintype "bidirectional"))
    )
    (net (code "121") (name "unconnected-(U1-ACBUS2-Pad28)") (class "Default")
      (node (ref "U1") (pin "28") (pinfunction "ACBUS2_28") (pintype "bidirectional"))
    )
    (net (code "122") (name "unconnected-(U1-ACBUS5-Pad32)") (class "Default")
      (node (ref "U1") (pin "32") (pinfunction "ACBUS5_32") (pintype "bidirectional"))
    )
    (net (code "123") (name "unconnected-(U1-ACBUS6-Pad33)") (class "Default")
      (node (ref "U1") (pin "33") (pinfunction "ACBUS6_33") (pintype "bidirectional"))
    )
    (net (code "124") (name "unconnected-(U1-ACBUS7-Pad34)") (class "Default")
      (node (ref "U1") (pin "34") (pinfunction "ACBUS7_34") (pintype "bidirectional"))
    )
    (net (code "125") (name "unconnected-(U1-BCBUS0-Pad48)") (class "Default")
      (node (ref "U1") (pin "48") (pinfunction "BCBUS0_48") (pintype "bidirectional"))
    )
    (net (code "126") (name "unconnected-(U1-BCBUS1-Pad52)") (class "Default")
      (node (ref "U1") (pin "52") (pinfunction "BCBUS1_52") (pintype "bidirectional"))
    )
    (net (code "127") (name "unconnected-(U1-BCBUS2-Pad53)") (class "Default")
      (node (ref "U1") (pin "53") (pinfunction "BCBUS2_53") (pintype "bidirectional"))
    )
    (net (code "128") (name "unconnected-(U1-BCBUS3-Pad54)") (class "Default")
      (node (ref "U1") (pin "54") (pinfunction "BCBUS3_54") (pintype "bidirectional"))
    )
    (net (code "129") (name "unconnected-(U1-BCBUS4-Pad55)") (class "Default")
      (node (ref "U1") (pin "55") (pinfunction "BCBUS4_55") (pintype "bidirectional"))
    )
    (net (code "130") (name "unconnected-(U1-BCBUS5-Pad57)") (class "Default")
      (node (ref "U1") (pin "57") (pinfunction "BCBUS5_57") (pintype "bidirectional"))
    )
    (net (code "131") (name "unconnected-(U1-BCBUS6-Pad58)") (class "Default")
      (node (ref "U1") (pin "58") (pinfunction "BCBUS6_58") (pintype "bidirectional"))
    )
    (net (code "132") (name "unconnected-(U1-BCBUS7-Pad59)") (class "Default")
      (node (ref "U1") (pin "59") (pinfunction "BCBUS7_59") (pintype "bidirectional"))
    )
    (net (code "133") (name "unconnected-(U1-~{SUSPEND}-Pad36)") (class "Default")
      (node (ref "U1") (pin "36") (pinfunction "~{SUSPEND}_36") (pintype "bidirectional"))
    )
  )
)
